# HFPB_01_PAGE-1.net
KiCad netlist of a schematic drawn in Altium Designer
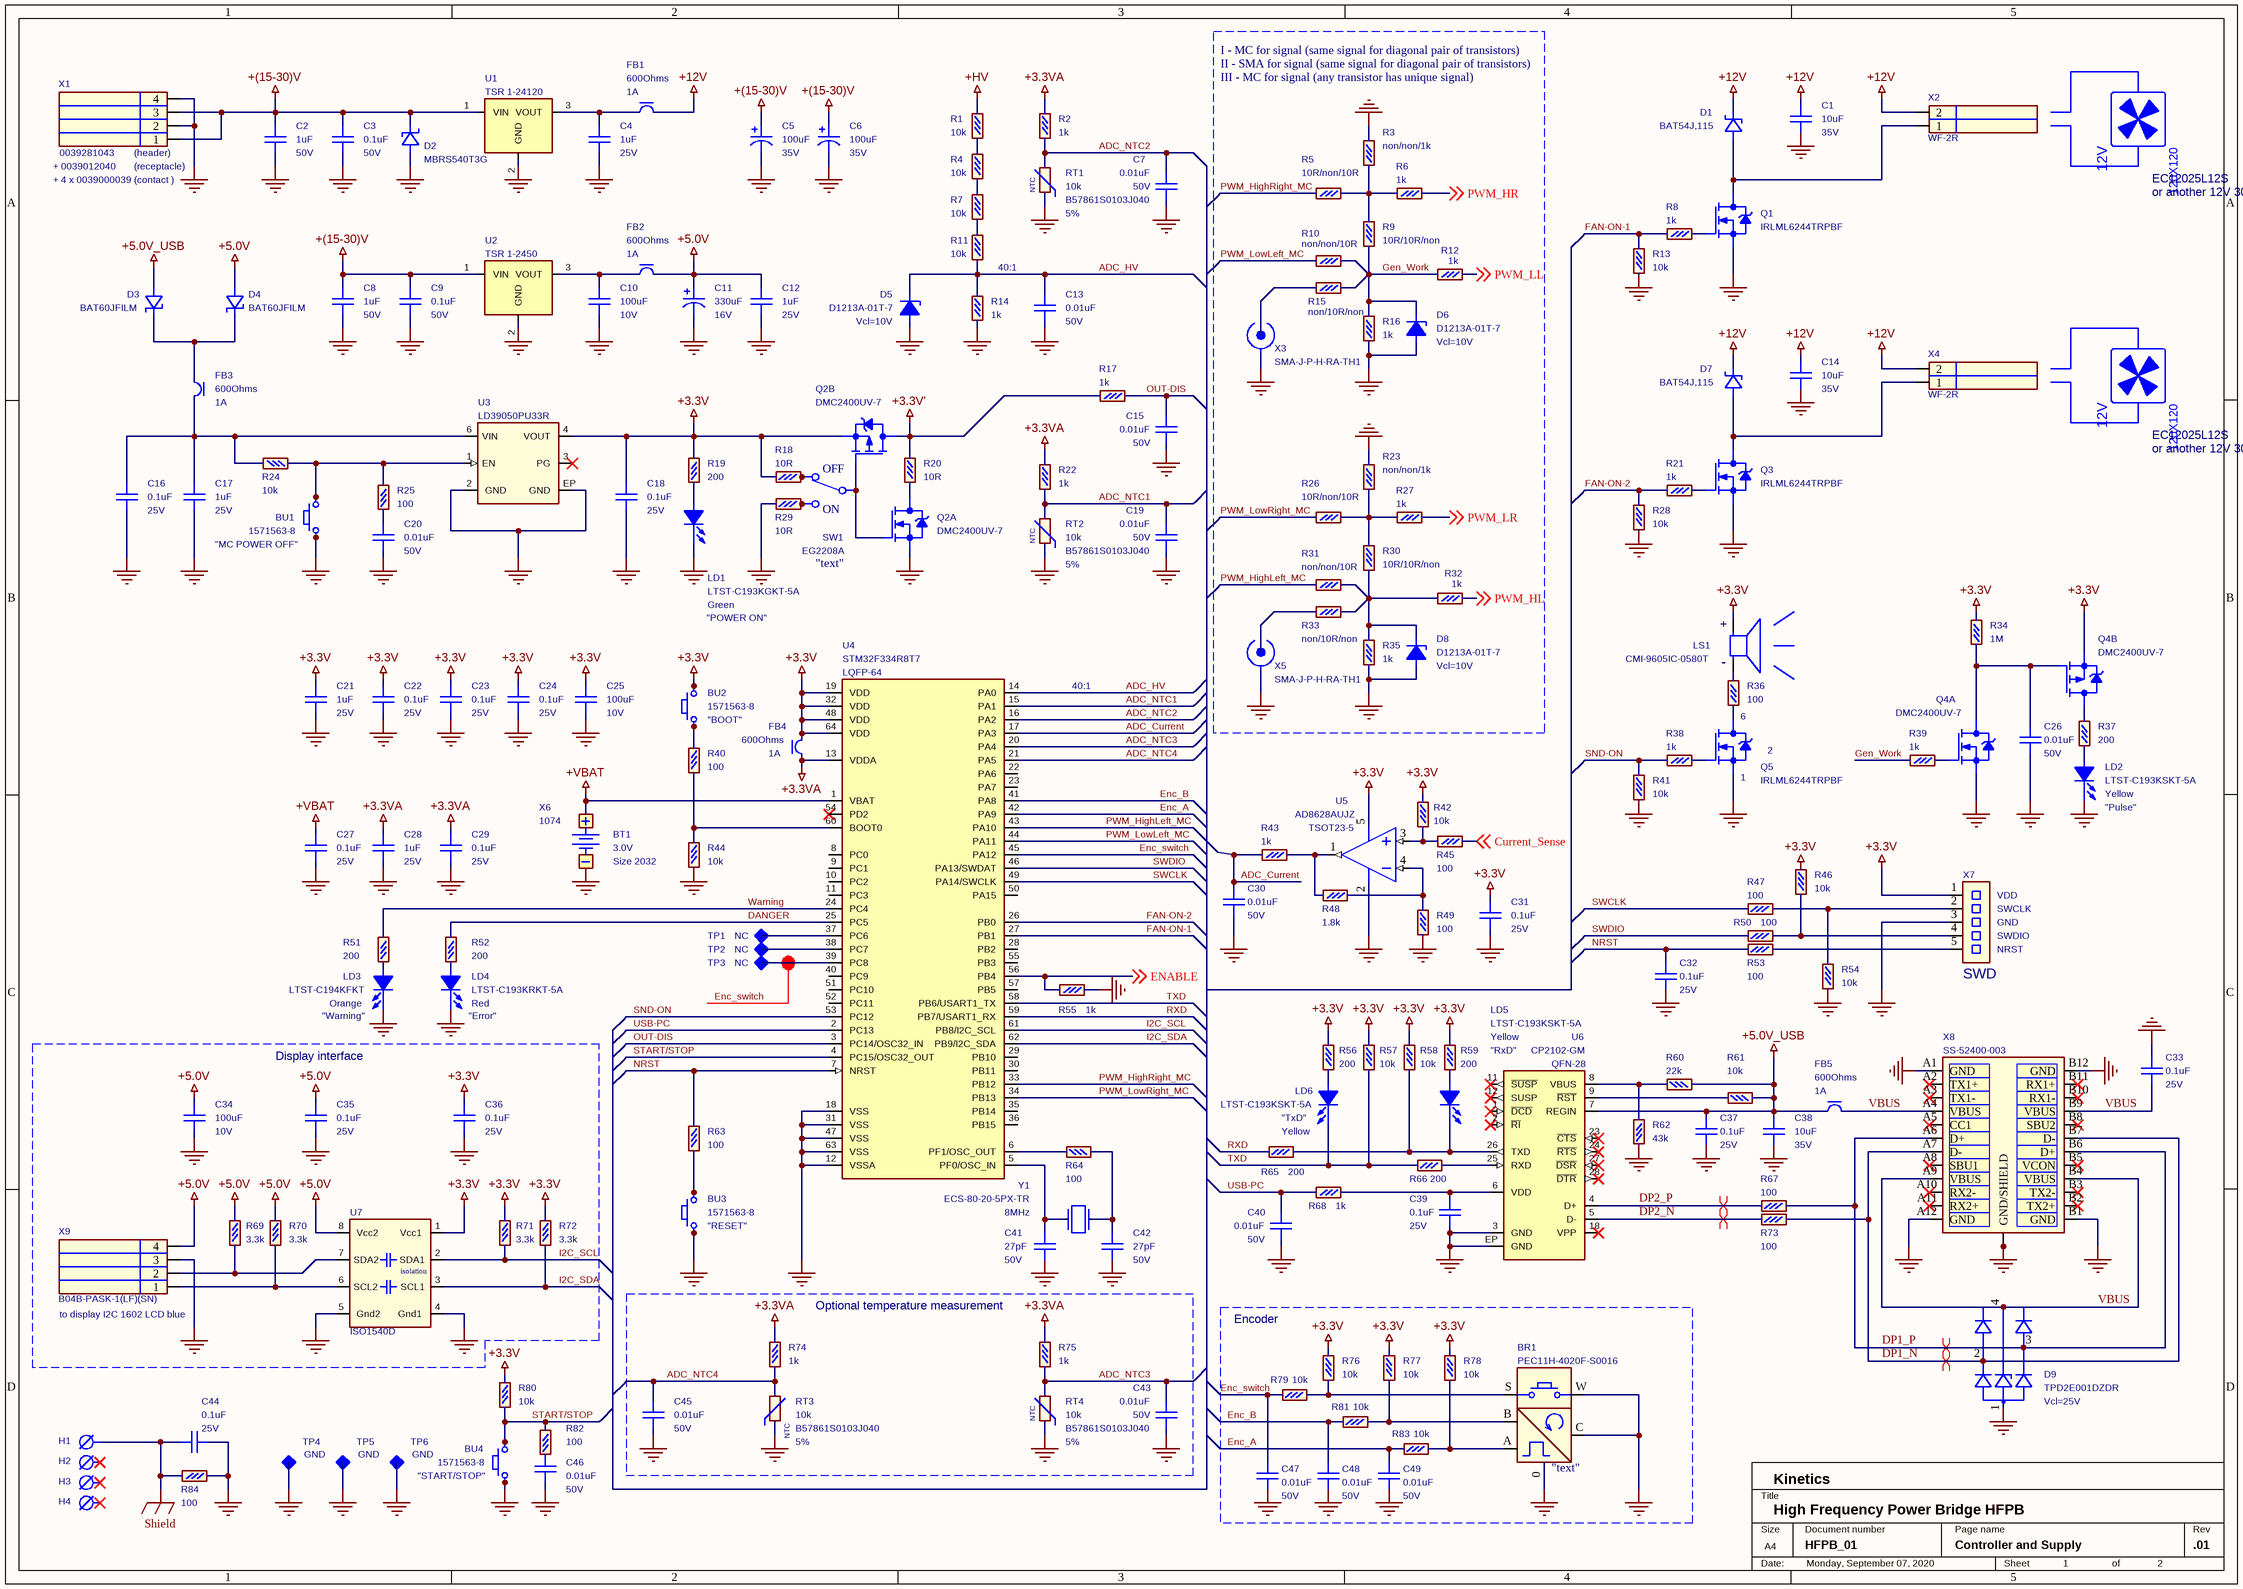
[diagram p0: HFPB_01, PAGE-1.SchDoc]

(export (version "E")
  (design (tool "Eeschema 10.0.6"))
  (components
    (comp (ref "BR1")
      (value "PEC11H-4020F-S0016")
      (footprint "BOURNS_PEC11H")
      (description "Encoder Mechanical 16 PPR")
      (fields (field (name "MANUFACTURER") "BOURNS") (field (name "ALTIUM_VALUE") "\"text\""))
      (libsource (lib "HFPB_01-SchLib") (part "PEC11H-4020F-S0016"))
    )
    (comp (ref "BT1")
      (value "3.0V")
      (description "Battery CR2032")
      (fields (field (name "MANUFACTURER") "* (Panasonic)"))
      (libsource (lib "HFPB_01-SchLib") (part "CR2032"))
    )
    (comp (ref "BU1")
      (value "1571563-8")
      (footprint "TE_1571563-8")
      (description "Switch tactile OFF-(ON) 0.05A 24V")
      (fields
        (field (name "MANUFACTURER") "TE Connectivity")
        (field (name "ALTIUM_VALUE") "\"MC POWER OFF\"")
      )
      (libsource (lib "HFPB_01-SchLib") (part "1571563-8"))
    )
    (comp (ref "BU2")
      (value "1571563-8")
      (footprint "TE_1571563-8")
      (description "Switch tactile OFF-(ON) 0.05A 24V")
      (fields (field (name "MANUFACTURER") "TE Connectivity") (field (name "ALTIUM_VALUE") "\"BOOT\""))
      (libsource (lib "HFPB_01-SchLib") (part "1571563-8"))
    )
    (comp (ref "BU3")
      (value "1571563-8")
      (footprint "TE_1571563-8")
      (description "Switch tactile OFF-(ON) 0.05A 24V")
      (fields (field (name "MANUFACTURER") "TE Connectivity") (field (name "ALTIUM_VALUE") "\"RESET\""))
      (libsource (lib "HFPB_01-SchLib") (part "1571563-8"))
    )
    (comp (ref "BU4")
      (value "1571563-8")
      (footprint "TE_1571563-8")
      (description "Switch tactile OFF-(ON) 0.05A 24V")
      (fields (field (name "MANUFACTURER") "TE Connectivity") (field (name "ALTIUM_VALUE") "\"START/STOP\""))
      (libsource (lib "HFPB_01-SchLib") (part "1571563-8"))
    )
    (comp (ref "C1")
      (value "10uF")
      (footprint "CAPC320X250X280L60N - full legend")
      (description "Capacitor 1210")
      (fields
        (field (name "PART NUMBER") "C1210C106M6PACTU")
        (field (name "MANUFACTURER") "KEMET")
        (field (name "VALUE3") "35V")
      )
      (libsource (lib "HFPB_01-SchLib") (part "C1210"))
    )
    (comp (ref "C2")
      (value "1uF")
      (footprint "CAPC160X80X80L35N - Full legend")
      (description "Capacitor 0603")
      (fields
        (field (name "PART NUMBER") "GRT188R61H105KE13D")
        (field (name "MANUFACTURER") "Murata")
        (field (name "VALUE3") "50V")
      )
      (libsource (lib "HFPB_01-SchLib") (part "C0603"))
    )
    (comp (ref "C3")
      (value "0.1uF")
      (footprint "CAPC160X80X80L35N - Full legend")
      (description "Capacitor 0603")
      (fields
        (field (name "PART NUMBER") "C0603C104K5RAC7082")
        (field (name "MANUFACTURER") "KEMET")
        (field (name "VALUE3") "50V")
      )
      (libsource (lib "HFPB_01-SchLib") (part "C0603"))
    )
    (comp (ref "C4")
      (value "1uF")
      (footprint "CAPC160X80X80L35N - Full legend")
      (description "Capacitor 0603")
      (fields
        (field (name "PART NUMBER") "C1608X7R1E105K080AB")
        (field (name "MANUFACTURER") "TDK")
        (field (name "VALUE3") "25V")
      )
      (libsource (lib "HFPB_01-SchLib") (part "C0603"))
    )
    (comp (ref "C5")
      (value "100uF")
      (footprint "CAPPRD350W60D850H900")
      (description "Capacitor Polymer Radial 100µF 35V 25mOhm")
      (fields
        (field (name "PART NUMBER") "RL81V101MDN1KX")
        (field (name "MANUFACTURER") "Nichicon")
        (field (name "VALUE3") "35V")
      )
      (libsource (lib "HFPB_01-SchLib") (part "RL81V101MDN1KX"))
    )
    (comp (ref "C6")
      (value "100uF")
      (footprint "CAPPRD350W60D850H900")
      (description "Capacitor Polymer Radial 100µF 35V 25mOhm")
      (fields
        (field (name "PART NUMBER") "RL81V101MDN1KX")
        (field (name "MANUFACTURER") "Nichicon")
        (field (name "VALUE3") "35V")
      )
      (libsource (lib "HFPB_01-SchLib") (part "RL81V101MDN1KX"))
    )
    (comp (ref "C7")
      (value "0.01uF")
      (footprint "CAPC160X80X80L35N - Full legend")
      (description "Capacitor 0603")
      (fields
        (field (name "PART NUMBER") "GRM1885C1H103JA01D")
        (field (name "MANUFACTURER") "Murata")
        (field (name "VALUE3") "50V")
      )
      (libsource (lib "HFPB_01-SchLib") (part "C0603"))
    )
    (comp (ref "C8")
      (value "1uF")
      (footprint "CAPC160X80X80L35N - Full legend")
      (description "Capacitor 0603")
      (fields
        (field (name "PART NUMBER") "GRT188R61H105KE13D")
        (field (name "MANUFACTURER") "Murata")
        (field (name "VALUE3") "50V")
      )
      (libsource (lib "HFPB_01-SchLib") (part "C0603"))
    )
    (comp (ref "C9")
      (value "0.1uF")
      (footprint "CAPC160X80X80L35N - Full legend")
      (description "Capacitor 0603")
      (fields
        (field (name "PART NUMBER") "C0603C104K5RAC7082")
        (field (name "MANUFACTURER") "KEMET")
        (field (name "VALUE3") "50V")
      )
      (libsource (lib "HFPB_01-SchLib") (part "C0603"))
    )
    (comp (ref "C10")
      (value "100uF")
      (footprint "CAPC320X250X280L60N - full legend")
      (description "Capacitor 1210")
      (fields
        (field (name "PART NUMBER") "C1210C107M8PACTU")
        (field (name "MANUFACTURER") "KEMET")
        (field (name "VALUE3") "10V")
      )
      (libsource (lib "HFPB_01-SchLib") (part "C1210"))
    )
    (comp (ref "C11")
      (value "330uF")
      (footprint "CAPPRD350W60D850H900")
      (description "Capacitor Polymer Radial 330µF 16V 12mOhm")
      (fields
        (field (name "PART NUMBER") "RL81C331MDN1KX")
        (field (name "MANUFACTURER") "Nichicon")
        (field (name "VALUE3") "16V")
      )
      (libsource (lib "HFPB_01-SchLib") (part "RL81C331MDN1KX"))
    )
    (comp (ref "C12")
      (value "1uF")
      (footprint "CAPC160X80X80L35N - Full legend")
      (description "Capacitor 0603")
      (fields
        (field (name "PART NUMBER") "C1608X7R1E105K080AB")
        (field (name "MANUFACTURER") "TDK")
        (field (name "VALUE3") "25V")
      )
      (libsource (lib "HFPB_01-SchLib") (part "C0603"))
    )
    (comp (ref "C13")
      (value "0.01uF")
      (footprint "CAPC160X80X80L35N - Full legend")
      (description "Capacitor 0603")
      (fields
        (field (name "PART NUMBER") "GRM1885C1H103JA01D")
        (field (name "MANUFACTURER") "Murata")
        (field (name "VALUE3") "50V")
      )
      (libsource (lib "HFPB_01-SchLib") (part "C0603"))
    )
    (comp (ref "C14")
      (value "10uF")
      (footprint "CAPC320X250X280L60N - full legend")
      (description "Capacitor 1210")
      (fields
        (field (name "PART NUMBER") "C1210C106M6PACTU")
        (field (name "MANUFACTURER") "KEMET")
        (field (name "VALUE3") "35V")
      )
      (libsource (lib "HFPB_01-SchLib") (part "C1210"))
    )
    (comp (ref "C15")
      (value "0.01uF")
      (footprint "CAPC160X80X80L35N - Full legend")
      (description "Capacitor 0603")
      (fields
        (field (name "PART NUMBER") "GRM1885C1H103JA01D")
        (field (name "MANUFACTURER") "Murata")
        (field (name "VALUE3") "50V")
      )
      (libsource (lib "HFPB_01-SchLib") (part "C0603"))
    )
    (comp (ref "C16")
      (value "0.1uF")
      (footprint "CAPC160X80X80L35N - Full legend")
      (description "Capacitor 0603")
      (fields
        (field (name "PART NUMBER") "C0603C104K3RAC7082")
        (field (name "MANUFACTURER") "KEMET")
        (field (name "VALUE3") "25V")
      )
      (libsource (lib "HFPB_01-SchLib") (part "C0603"))
    )
    (comp (ref "C17")
      (value "1uF")
      (footprint "CAPC160X80X80L35N - Full legend")
      (description "Capacitor 0603")
      (fields
        (field (name "PART NUMBER") "C1608X7R1E105K080AB")
        (field (name "MANUFACTURER") "TDK")
        (field (name "VALUE3") "25V")
      )
      (libsource (lib "HFPB_01-SchLib") (part "C0603"))
    )
    (comp (ref "C18")
      (value "0.1uF")
      (footprint "CAPC160X80X80L35N - Full legend")
      (description "Capacitor 0603")
      (fields
        (field (name "PART NUMBER") "C0603C104K3RAC7082")
        (field (name "MANUFACTURER") "KEMET")
        (field (name "VALUE3") "25V")
      )
      (libsource (lib "HFPB_01-SchLib") (part "C0603"))
    )
    (comp (ref "C19")
      (value "0.01uF")
      (footprint "CAPC160X80X80L35N - Full legend")
      (description "Capacitor 0603")
      (fields
        (field (name "PART NUMBER") "GRM1885C1H103JA01D")
        (field (name "MANUFACTURER") "Murata")
        (field (name "VALUE3") "50V")
      )
      (libsource (lib "HFPB_01-SchLib") (part "C0603"))
    )
    (comp (ref "C20")
      (value "0.01uF")
      (footprint "CAPC160X80X80L35N - Full legend")
      (description "Capacitor 0603")
      (fields
        (field (name "PART NUMBER") "GRM1885C1H103JA01D")
        (field (name "MANUFACTURER") "Murata")
        (field (name "VALUE3") "50V")
      )
      (libsource (lib "HFPB_01-SchLib") (part "C0603"))
    )
    (comp (ref "C21")
      (value "1uF")
      (footprint "CAPC160X80X80L35N - Full legend")
      (description "Capacitor 0603")
      (fields
        (field (name "PART NUMBER") "C1608X7R1E105K080AB")
        (field (name "MANUFACTURER") "TDK")
        (field (name "VALUE3") "25V")
      )
      (libsource (lib "HFPB_01-SchLib") (part "C0603"))
    )
    (comp (ref "C22")
      (value "0.1uF")
      (footprint "CAPC160X80X80L35N - Full legend")
      (description "Capacitor 0603")
      (fields
        (field (name "PART NUMBER") "C0603C104K3RAC7082")
        (field (name "MANUFACTURER") "KEMET")
        (field (name "VALUE3") "25V")
      )
      (libsource (lib "HFPB_01-SchLib") (part "C0603"))
    )
    (comp (ref "C23")
      (value "0.1uF")
      (footprint "CAPC160X80X80L35N - Full legend")
      (description "Capacitor 0603")
      (fields
        (field (name "PART NUMBER") "C0603C104K3RAC7082")
        (field (name "MANUFACTURER") "KEMET")
        (field (name "VALUE3") "25V")
      )
      (libsource (lib "HFPB_01-SchLib") (part "C0603"))
    )
    (comp (ref "C24")
      (value "0.1uF")
      (footprint "CAPC160X80X80L35N - Full legend")
      (description "Capacitor 0603")
      (fields
        (field (name "PART NUMBER") "C0603C104K3RAC7082")
        (field (name "MANUFACTURER") "KEMET")
        (field (name "VALUE3") "25V")
      )
      (libsource (lib "HFPB_01-SchLib") (part "C0603"))
    )
    (comp (ref "C25")
      (value "100uF")
      (footprint "CAPC320X250X280L60N - full legend")
      (description "Capacitor 1210")
      (fields
        (field (name "PART NUMBER") "C1210C107M8PACTU")
        (field (name "MANUFACTURER") "KEMET")
        (field (name "VALUE3") "10V")
      )
      (libsource (lib "HFPB_01-SchLib") (part "C1210"))
    )
    (comp (ref "C26")
      (value "0.01uF")
      (footprint "CAPC160X80X80L35N - Full legend")
      (description "Capacitor 0603")
      (fields
        (field (name "PART NUMBER") "GRM1885C1H103JA01D")
        (field (name "MANUFACTURER") "Murata")
        (field (name "VALUE3") "50V")
      )
      (libsource (lib "HFPB_01-SchLib") (part "C0603"))
    )
    (comp (ref "C27")
      (value "0.1uF")
      (footprint "CAPC160X80X80L35N - Full legend")
      (description "Capacitor 0603")
      (fields
        (field (name "PART NUMBER") "C0603C104K3RAC7082")
        (field (name "MANUFACTURER") "KEMET")
        (field (name "VALUE3") "25V")
      )
      (libsource (lib "HFPB_01-SchLib") (part "C0603"))
    )
    (comp (ref "C28")
      (value "1uF")
      (footprint "CAPC160X80X80L35N - Full legend")
      (description "Capacitor 0603")
      (fields
        (field (name "PART NUMBER") "C1608X7R1E105K080AB")
        (field (name "MANUFACTURER") "TDK")
        (field (name "VALUE3") "25V")
      )
      (libsource (lib "HFPB_01-SchLib") (part "C0603"))
    )
    (comp (ref "C29")
      (value "0.1uF")
      (footprint "CAPC160X80X80L35N - Full legend")
      (description "Capacitor 0603")
      (fields
        (field (name "PART NUMBER") "C0603C104K3RAC7082")
        (field (name "MANUFACTURER") "KEMET")
        (field (name "VALUE3") "25V")
      )
      (libsource (lib "HFPB_01-SchLib") (part "C0603"))
    )
    (comp (ref "C30")
      (value "0.01uF")
      (footprint "CAPC160X80X80L35N - Full legend")
      (description "Capacitor 0603")
      (fields
        (field (name "PART NUMBER") "GRM1885C1H103JA01D")
        (field (name "MANUFACTURER") "Murata")
        (field (name "VALUE3") "50V")
      )
      (libsource (lib "HFPB_01-SchLib") (part "C0603"))
    )
    (comp (ref "C31")
      (value "0.1uF")
      (footprint "CAPC160X80X80L35N - Full legend")
      (description "Capacitor 0603")
      (fields
        (field (name "PART NUMBER") "C0603C104K3RAC7082")
        (field (name "MANUFACTURER") "KEMET")
        (field (name "VALUE3") "25V")
      )
      (libsource (lib "HFPB_01-SchLib") (part "C0603"))
    )
    (comp (ref "C32")
      (value "0.1uF")
      (footprint "CAPC160X80X80L35N - Full legend")
      (description "Capacitor 0603")
      (fields
        (field (name "PART NUMBER") "C0603C104K3RAC7082")
        (field (name "MANUFACTURER") "KEMET")
        (field (name "VALUE3") "25V")
      )
      (libsource (lib "HFPB_01-SchLib") (part "C0603"))
    )
    (comp (ref "C33")
      (value "0.1uF")
      (footprint "CAPC160X80X80L35N - Full legend")
      (description "Capacitor 0603")
      (fields
        (field (name "PART NUMBER") "C0603C104K3RAC7082")
        (field (name "MANUFACTURER") "KEMET")
        (field (name "VALUE3") "25V")
      )
      (libsource (lib "HFPB_01-SchLib") (part "C0603"))
    )
    (comp (ref "C34")
      (value "100uF")
      (footprint "CAPC320X250X280L60N - full legend")
      (description "Capacitor 1210")
      (fields
        (field (name "PART NUMBER") "C1210C107M8PACTU")
        (field (name "MANUFACTURER") "KEMET")
        (field (name "VALUE3") "10V")
      )
      (libsource (lib "HFPB_01-SchLib") (part "C1210"))
    )
    (comp (ref "C35")
      (value "0.1uF")
      (footprint "CAPC160X80X80L35N - Full legend")
      (description "Capacitor 0603")
      (fields
        (field (name "PART NUMBER") "C0603C104K3RAC7082")
        (field (name "MANUFACTURER") "KEMET")
        (field (name "VALUE3") "25V")
      )
      (libsource (lib "HFPB_01-SchLib") (part "C0603"))
    )
    (comp (ref "C36")
      (value "0.1uF")
      (footprint "CAPC160X80X80L35N - Full legend")
      (description "Capacitor 0603")
      (fields
        (field (name "PART NUMBER") "C0603C104K3RAC7082")
        (field (name "MANUFACTURER") "KEMET")
        (field (name "VALUE3") "25V")
      )
      (libsource (lib "HFPB_01-SchLib") (part "C0603"))
    )
    (comp (ref "C37")
      (value "0.1uF")
      (footprint "CAPC160X80X80L35N - Full legend")
      (description "Capacitor 0603")
      (fields
        (field (name "PART NUMBER") "C0603C104K3RAC7082")
        (field (name "MANUFACTURER") "KEMET")
        (field (name "VALUE3") "25V")
      )
      (libsource (lib "HFPB_01-SchLib") (part "C0603"))
    )
    (comp (ref "C38")
      (value "10uF")
      (footprint "CAPC320X250X280L60N - full legend")
      (description "Capacitor 1210")
      (fields
        (field (name "PART NUMBER") "C1210C106M6PACTU")
        (field (name "MANUFACTURER") "KEMET")
        (field (name "VALUE3") "35V")
      )
      (libsource (lib "HFPB_01-SchLib") (part "C1210"))
    )
    (comp (ref "C39")
      (value "0.1uF")
      (footprint "CAPC160X80X80L35N - Full legend")
      (description "Capacitor 0603")
      (fields
        (field (name "PART NUMBER") "C0603C104K3RAC7082")
        (field (name "MANUFACTURER") "KEMET")
        (field (name "VALUE3") "25V")
      )
      (libsource (lib "HFPB_01-SchLib") (part "C0603"))
    )
    (comp (ref "C40")
      (value "0.01uF")
      (footprint "CAPC160X80X80L35N - Full legend")
      (description "Capacitor 0603")
      (fields
        (field (name "PART NUMBER") "GRM1885C1H103JA01D")
        (field (name "MANUFACTURER") "Murata")
        (field (name "VALUE3") "50V")
      )
      (libsource (lib "HFPB_01-SchLib") (part "C0603"))
    )
    (comp (ref "C41")
      (value "27pF")
      (footprint "CAPC160X80X80L35N - Full legend")
      (description "Capacitor 0603")
      (fields
        (field (name "PART NUMBER") "C0603C270J5GAC7411")
        (field (name "MANUFACTURER") "KEMET")
        (field (name "VALUE3") "50V")
      )
      (libsource (lib "HFPB_01-SchLib") (part "C0603"))
    )
    (comp (ref "C42")
      (value "27pF")
      (footprint "CAPC160X80X80L35N - Full legend")
      (description "Capacitor 0603")
      (fields
        (field (name "PART NUMBER") "C0603C270J5GAC7411")
        (field (name "MANUFACTURER") "KEMET")
        (field (name "VALUE3") "50V")
      )
      (libsource (lib "HFPB_01-SchLib") (part "C0603"))
    )
    (comp (ref "C43")
      (value "0.01uF")
      (footprint "CAPC160X80X80L35N - Full legend")
      (description "Capacitor 0603")
      (fields
        (field (name "PART NUMBER") "GRM1885C1H103JA01D")
        (field (name "MANUFACTURER") "Murata")
        (field (name "VALUE3") "50V")
      )
      (libsource (lib "HFPB_01-SchLib") (part "C0603"))
    )
    (comp (ref "C44")
      (value "0.1uF")
      (footprint "CAPC160X80X80L35N - Full legend")
      (description "Capacitor 0603")
      (fields
        (field (name "PART NUMBER") "C0603C104K3RAC7082")
        (field (name "MANUFACTURER") "KEMET")
        (field (name "VALUE3") "25V")
      )
      (libsource (lib "HFPB_01-SchLib") (part "C0603"))
    )
    (comp (ref "C45")
      (value "0.01uF")
      (footprint "CAPC160X80X80L35N - Full legend")
      (description "Capacitor 0603")
      (fields
        (field (name "PART NUMBER") "GRM1885C1H103JA01D")
        (field (name "MANUFACTURER") "Murata")
        (field (name "VALUE3") "50V")
      )
      (libsource (lib "HFPB_01-SchLib") (part "C0603"))
    )
    (comp (ref "C46")
      (value "0.01uF")
      (footprint "CAPC160X80X80L35N - Full legend")
      (description "Capacitor 0603")
      (fields
        (field (name "PART NUMBER") "GRM1885C1H103JA01D")
        (field (name "MANUFACTURER") "Murata")
        (field (name "VALUE3") "50V")
      )
      (libsource (lib "HFPB_01-SchLib") (part "C0603"))
    )
    (comp (ref "C47")
      (value "0.01uF")
      (footprint "CAPC160X80X80L35N - Full legend")
      (description "Capacitor 0603")
      (fields
        (field (name "PART NUMBER") "GRM1885C1H103JA01D")
        (field (name "MANUFACTURER") "Murata")
        (field (name "VALUE3") "50V")
      )
      (libsource (lib "HFPB_01-SchLib") (part "C0603"))
    )
    (comp (ref "C48")
      (value "0.01uF")
      (footprint "CAPC160X80X80L35N - Full legend")
      (description "Capacitor 0603")
      (fields
        (field (name "PART NUMBER") "GRM1885C1H103JA01D")
        (field (name "MANUFACTURER") "Murata")
        (field (name "VALUE3") "50V")
      )
      (libsource (lib "HFPB_01-SchLib") (part "C0603"))
    )
    (comp (ref "C49")
      (value "0.01uF")
      (footprint "CAPC160X80X80L35N - Full legend")
      (description "Capacitor 0603")
      (fields
        (field (name "PART NUMBER") "GRM1885C1H103JA01D")
        (field (name "MANUFACTURER") "Murata")
        (field (name "VALUE3") "50V")
      )
      (libsource (lib "HFPB_01-SchLib") (part "C0603"))
    )
    (comp (ref "D1")
      (value "BAT54J,115")
      (footprint "SODFL250X125X80L40X32N")
      (description "Diode Schottky 30V 0.2A")
      (fields (field (name "MANUFACTURER") "Nexperia"))
      (libsource (lib "HFPB_01-SchLib") (part "BAT54J,115"))
    )
    (comp (ref "D2")
      (value "MBRS540T3G")
      (footprint "DIOM795X585X240L100X300N")
      (description "Diode Schottky 40V 5A")
      (fields (field (name "MANUFACTURER") "ON Semiconductor"))
      (libsource (lib "HFPB_01-SchLib") (part "MBRS540T3G"))
    )
    (comp (ref "D3")
      (value "BAT60JFILM")
      (footprint "SOD250X125X110L30X32N")
      (description "Diode Schottky 10V 3A")
      (fields (field (name "MANUFACTURER") "STM"))
      (libsource (lib "HFPB_01-SchLib") (part "BAT60JFILM"))
    )
    (comp (ref "D4")
      (value "BAT60JFILM")
      (footprint "SOD250X125X110L30X32N")
      (description "Diode Schottky 10V 3A")
      (fields (field (name "MANUFACTURER") "STM"))
      (libsource (lib "HFPB_01-SchLib") (part "BAT60JFILM"))
    )
    (comp (ref "D5")
      (value "D1213A-01T-7")
      (footprint "SODFL160X80X65L30X30N")
      (description "TVS Diode Vstand=3.3V Vclamp=10V")
      (fields (field (name "MANUFACTURER") "Diodes Inc.") (field (name "VALUE2") "Vcl=10V"))
      (libsource (lib "HFPB_01-SchLib") (part "D1213A-01T-7"))
    )
    (comp (ref "D6")
      (value "D1213A-01T-7")
      (footprint "SODFL160X80X65L30X30N")
      (description "TVS Diode Vstand=3.3V Vclamp=10V")
      (fields (field (name "MANUFACTURER") "Diodes Inc.") (field (name "VALUE2") "Vcl=10V"))
      (libsource (lib "HFPB_01-SchLib") (part "D1213A-01T-7"))
    )
    (comp (ref "D7")
      (value "BAT54J,115")
      (footprint "SODFL250X125X80L40X32N")
      (description "Diode Schottky 30V 0.2A")
      (fields (field (name "MANUFACTURER") "Nexperia"))
      (libsource (lib "HFPB_01-SchLib") (part "BAT54J,115"))
    )
    (comp (ref "D8")
      (value "D1213A-01T-7")
      (footprint "SODFL160X80X65L30X30N")
      (description "TVS Diode Vstand=3.3V Vclamp=10V")
      (fields (field (name "MANUFACTURER") "Diodes Inc.") (field (name "VALUE2") "Vcl=10V"))
      (libsource (lib "HFPB_01-SchLib") (part "D1213A-01T-7"))
    )
    (comp (ref "D9")
      (value "TPD2E001DZDR")
      (footprint "SOT143-4P192_237X122L40X40N")
      (description "TVS Diode Vstand=5.5V Vbr=11V")
      (fields (field (name "MANUFACTURER") "Texas Instruments") (field (name "VALUE2") "Vcl=25V"))
      (libsource (lib "HFPB_01-SchLib") (part "TPD2E001DZDR"))
    )
    (comp (ref "FB1")
      (value "600Ohms")
      (footprint "BEADC160X80X80L30N")
      (description "Ferrite Bead 600Ohms 1A")
      (fields
        (field (name "PART NUMBER") "MPZ1608S601ATA00")
        (field (name "MANUFACTURER") "TDK")
        (field (name "VALUE1") "1A")
      )
      (libsource (lib "HFPB_01-SchLib") (part "MPZ1608S601ATA00"))
    )
    (comp (ref "FB2")
      (value "600Ohms")
      (footprint "BEADC160X80X80L30N")
      (description "Ferrite Bead 600Ohms 1A")
      (fields
        (field (name "PART NUMBER") "MPZ1608S601ATA00")
        (field (name "MANUFACTURER") "TDK")
        (field (name "VALUE1") "1A")
      )
      (libsource (lib "HFPB_01-SchLib") (part "MPZ1608S601ATA00"))
    )
    (comp (ref "FB3")
      (value "600Ohms")
      (footprint "BEADC160X80X80L30N")
      (description "Ferrite Bead 600Ohms 1A")
      (fields
        (field (name "PART NUMBER") "MPZ1608S601ATA00")
        (field (name "MANUFACTURER") "TDK")
        (field (name "VALUE1") "1A")
      )
      (libsource (lib "HFPB_01-SchLib") (part "MPZ1608S601ATA00"))
    )
    (comp (ref "FB4")
      (value "600Ohms")
      (footprint "BEADC160X80X80L30N")
      (description "Ferrite Bead 600Ohms 1A")
      (fields
        (field (name "PART NUMBER") "MPZ1608S601ATA00")
        (field (name "MANUFACTURER") "TDK")
        (field (name "VALUE1") "1A")
      )
      (libsource (lib "HFPB_01-SchLib") (part "MPZ1608S601ATA00"))
    )
    (comp (ref "FB5")
      (value "600Ohms")
      (footprint "BEADC160X80X80L30N")
      (description "Ferrite Bead 600Ohms 1A")
      (fields
        (field (name "PART NUMBER") "MPZ1608S601ATA00")
        (field (name "MANUFACTURER") "TDK")
        (field (name "VALUE1") "1A")
      )
      (libsource (lib "HFPB_01-SchLib") (part "MPZ1608S601ATA00"))
    )
    (comp (ref "H1")
      (value "~")
      (footprint "hole/3.5/4.5-O")
      (description "HOLE 3.5mm")
      (libsource (lib "HFPB_01-SchLib") (part "HOLE/3.5"))
    )
    (comp (ref "H2")
      (value "~")
      (footprint "hole/3.5/4.5-O")
      (description "HOLE 3.5mm")
      (libsource (lib "HFPB_01-SchLib") (part "HOLE/3.5"))
    )
    (comp (ref "H3")
      (value "~")
      (footprint "hole/3.5/4.5-O")
      (description "HOLE 3.5mm")
      (libsource (lib "HFPB_01-SchLib") (part "HOLE/3.5"))
    )
    (comp (ref "H4")
      (value "~")
      (footprint "hole/3.5/4.5-O")
      (description "HOLE 3.5mm")
      (libsource (lib "HFPB_01-SchLib") (part "HOLE/3.5"))
    )
    (comp (ref "LD1")
      (value "LTST-C193KGKT-5A")
      (footprint "LEDC160X80X40L30N")
      (description "LED 0603")
      (fields
        (field (name "MANUFACTURER") "Lite-On Inc.")
        (field (name "ALTIUM_VALUE") "Green")
        (field (name "TEXT") "\"POWER ON\"")
      )
      (libsource (lib "HFPB_01-SchLib") (part "LED0603"))
    )
    (comp (ref "LD2")
      (value "LTST-C193KSKT-5A")
      (footprint "LEDC160X80X40L30N")
      (description "LED 0603")
      (fields
        (field (name "MANUFACTURER") "Lite-On Inc.")
        (field (name "TEXT") "\"Pulse\"")
        (field (name "ALTIUM_VALUE") "Yellow")
      )
      (libsource (lib "HFPB_01-SchLib") (part "LED0603"))
    )
    (comp (ref "LD3")
      (value "LTST-C194KFKT")
      (footprint "LEDC160X80X40L30N")
      (description "LED 0603")
      (fields
        (field (name "MANUFACTURER") "Lite-On Inc.")
        (field (name "ALTIUM_VALUE") "Orange")
        (field (name "TEXT") "\"Warning\"")
      )
      (libsource (lib "HFPB_01-SchLib") (part "LED0603"))
    )
    (comp (ref "LD4")
      (value "LTST-C193KRKT-5A")
      (footprint "LEDC160X80X40L30N")
      (description "LED 0603")
      (fields
        (field (name "MANUFACTURER") "Lite-On Inc.")
        (field (name "ALTIUM_VALUE") "Red")
        (field (name "TEXT") "\"Error\"")
      )
      (libsource (lib "HFPB_01-SchLib") (part "LED0603"))
    )
    (comp (ref "LD5")
      (value "LTST-C193KSKT-5A")
      (footprint "LEDC160X80X40L30N")
      (description "LED 0603")
      (fields
        (field (name "MANUFACTURER") "Lite-On Inc.")
        (field (name "TEXT") "\"RxD\"")
        (field (name "ALTIUM_VALUE") "Yellow")
      )
      (libsource (lib "HFPB_01-SchLib") (part "LED0603"))
    )
    (comp (ref "LD6")
      (value "LTST-C193KSKT-5A")
      (footprint "LEDC160X80X40L30N")
      (description "LED 0603")
      (fields
        (field (name "MANUFACTURER") "Lite-On Inc.")
        (field (name "TEXT") "\"TxD\"")
        (field (name "ALTIUM_VALUE") "Yellow")
      )
      (libsource (lib "HFPB_01-SchLib") (part "LED0603"))
    )
    (comp (ref "LS1")
      (value "CMI-9605IC-0580T")
      (footprint "CUI_CMI-9605IC-0580T")
      (description "Buzzer Magnetic Audio Indicator 5V 80dB 2.7kHz")
      (fields (field (name "MANUFACTURER") "CUI"))
      (libsource (lib "HFPB_01-SchLib") (part "CMI-9605IC-0580T"))
    )
    (comp (ref "Q1")
      (value "IRLML6244TRPBF")
      (footprint "SOT23-3P95_235X110L50X40N")
      (description "MOSFET N-channel, 20V, 21mOhm")
      (fields (field (name "MANUFACTURER") "Infineon"))
      (libsource (lib "HFPB_01-SchLib") (part "IRLML6244TRPBF"))
    )
    (comp (ref "Q2")
      (value "DMC2400UV-7")
      (footprint "TRXSOFL6P50_160X162X60L20X22N")
      (description "Transistors N-channel, P-channel (Dual) MOSFET, 20V, 1A")
      (fields (field (name "MANUFACTURER") "Diodes Inc."))
      (libsource (lib "HFPB_01-SchLib") (part "DMC2400UV-7"))
    )
    (comp (ref "Q3")
      (value "IRLML6244TRPBF")
      (footprint "SOT23-3P95_235X110L50X40N")
      (description "MOSFET N-channel, 20V, 21mOhm")
      (fields (field (name "MANUFACTURER") "Infineon"))
      (libsource (lib "HFPB_01-SchLib") (part "IRLML6244TRPBF"))
    )
    (comp (ref "Q4")
      (value "DMC2400UV-7")
      (footprint "TRXSOFL6P50_160X162X60L20X22N")
      (description "Transistors N-channel, P-channel (Dual) MOSFET, 20V, 1A")
      (fields (field (name "MANUFACTURER") "Diodes Inc."))
      (libsource (lib "HFPB_01-SchLib") (part "DMC2400UV-7"))
    )
    (comp (ref "Q5")
      (value "IRLML6244TRPBF")
      (footprint "SOT23-3P95_235X110L50X40N")
      (description "MOSFET N-channel, 20V, 21mOhm")
      (fields (field (name "MANUFACTURER") "Infineon"))
      (libsource (lib "HFPB_01-SchLib") (part "IRLML6244TRPBF"))
    )
    (comp (ref "R1")
      (value "10k")
      (footprint "RESC160X80X55L30N - Full legend")
      (description "Resistor 0603")
      (fields (field (name "PART NUMBER") "ERJ-3EKF1002V") (field (name "MANUFACTURER") "Panasonic"))
      (libsource (lib "HFPB_01-SchLib") (part "R0603"))
    )
    (comp (ref "R2")
      (value "1k")
      (footprint "RESC160X80X55L30N - Full legend")
      (description "Resistor 0603")
      (fields (field (name "PART NUMBER") "ERJ-3EKF1001V") (field (name "MANUFACTURER") "Panasonic"))
      (libsource (lib "HFPB_01-SchLib") (part "R0603"))
    )
    (comp (ref "R3")
      (value "non/non/1k")
      (footprint "RESC160X80X55L30N - Full legend")
      (description "Resistor 0603")
      (fields (field (name "PART NUMBER") "ERJ-3EKF1001V") (field (name "MANUFACTURER") "Panasonic"))
      (libsource (lib "") (part "R0603_3"))
    )
    (comp (ref "R4")
      (value "10k")
      (footprint "RESC160X80X55L30N - Full legend")
      (description "Resistor 0603")
      (fields (field (name "PART NUMBER") "ERJ-3EKF1002V") (field (name "MANUFACTURER") "Panasonic"))
      (libsource (lib "HFPB_01-SchLib") (part "R0603"))
    )
    (comp (ref "R5")
      (value "10R/non/10R")
      (footprint "RESC160X80X55L30N - Full legend")
      (description "Resistor 0603")
      (fields (field (name "PART NUMBER") "ERJ-3EKF10R0V") (field (name "MANUFACTURER") "Panasonic"))
      (libsource (lib "") (part "R0603_1"))
    )
    (comp (ref "R6")
      (value "1k")
      (footprint "RESC160X80X55L30N - Full legend")
      (description "Resistor 0603")
      (fields (field (name "PART NUMBER") "ERJ-3EKF1001V") (field (name "MANUFACTURER") "Panasonic"))
      (libsource (lib "") (part "R0603_1"))
    )
    (comp (ref "R7")
      (value "10k")
      (footprint "RESC160X80X55L30N - Full legend")
      (description "Resistor 0603")
      (fields (field (name "PART NUMBER") "ERJ-3EKF1002V") (field (name "MANUFACTURER") "Panasonic"))
      (libsource (lib "HFPB_01-SchLib") (part "R0603"))
    )
    (comp (ref "R8")
      (value "1k")
      (footprint "RESC160X80X55L30N - Full legend")
      (description "Resistor 0603")
      (fields (field (name "PART NUMBER") "ERJ-3EKF1001V") (field (name "MANUFACTURER") "Panasonic"))
      (libsource (lib "") (part "R0603_1"))
    )
    (comp (ref "R9")
      (value "10R/10R/non")
      (footprint "RESC160X80X55L30N - Full legend")
      (description "Resistor 0603")
      (fields (field (name "PART NUMBER") "ERJ-3EKF10R0V") (field (name "MANUFACTURER") "Panasonic"))
      (libsource (lib "HFPB_01-SchLib") (part "R0603"))
    )
    (comp (ref "R10")
      (value "non/non/10R")
      (footprint "RESC160X80X55L30N - Full legend")
      (description "Resistor 0603")
      (fields (field (name "PART NUMBER") "ERJ-3EKF10R0V") (field (name "MANUFACTURER") "Panasonic"))
      (libsource (lib "") (part "R0603_1"))
    )
    (comp (ref "R11")
      (value "10k")
      (footprint "RESC160X80X55L30N - Full legend")
      (description "Resistor 0603")
      (fields (field (name "PART NUMBER") "ERJ-3EKF1002V") (field (name "MANUFACTURER") "Panasonic"))
      (libsource (lib "HFPB_01-SchLib") (part "R0603"))
    )
    (comp (ref "R12")
      (value "1k")
      (footprint "RESC160X80X55L30N - Full legend")
      (description "Resistor 0603")
      (fields (field (name "PART NUMBER") "ERJ-3EKF1001V") (field (name "MANUFACTURER") "Panasonic"))
      (libsource (lib "") (part "R0603_1"))
    )
    (comp (ref "R13")
      (value "10k")
      (footprint "RESC160X80X55L30N - Full legend")
      (description "Resistor 0603")
      (fields (field (name "PART NUMBER") "ERJ-3EKF1002V") (field (name "MANUFACTURER") "Panasonic"))
      (libsource (lib "HFPB_01-SchLib") (part "R0603"))
    )
    (comp (ref "R14")
      (value "1k")
      (footprint "RESC160X80X55L30N - Full legend")
      (description "Resistor 0603")
      (fields (field (name "PART NUMBER") "ERJ-3EKF1001V") (field (name "MANUFACTURER") "Panasonic"))
      (libsource (lib "HFPB_01-SchLib") (part "R0603"))
    )
    (comp (ref "R15")
      (value "non/10R/non")
      (footprint "RESC160X80X55L30N - Full legend")
      (description "Resistor 0603")
      (fields (field (name "PART NUMBER") "ERJ-3EKF10R0V") (field (name "MANUFACTURER") "Panasonic"))
      (libsource (lib "") (part "R0603_1"))
    )
    (comp (ref "R16")
      (value "1k")
      (footprint "RESC160X80X55L30N - Full legend")
      (description "Resistor 0603")
      (fields (field (name "PART NUMBER") "ERJ-3EKF1001V") (field (name "MANUFACTURER") "Panasonic"))
      (libsource (lib "") (part "R0603_3"))
    )
    (comp (ref "R17")
      (value "1k")
      (footprint "RESC160X80X55L30N - Full legend")
      (description "Resistor 0603")
      (fields (field (name "PART NUMBER") "ERJ-3EKF1001V") (field (name "MANUFACTURER") "Panasonic"))
      (libsource (lib "") (part "R0603_1"))
    )
    (comp (ref "R18")
      (value "10R")
      (footprint "RESC160X80X55L30N - Full legend")
      (description "Resistor 0603")
      (fields (field (name "PART NUMBER") "ERJ-3EKF10R0V") (field (name "MANUFACTURER") "Panasonic"))
      (libsource (lib "") (part "R0603_2"))
    )
    (comp (ref "R19")
      (value "200")
      (footprint "RESC160X80X55L30N - Full legend")
      (description "Resistor 0603")
      (fields (field (name "PART NUMBER") "ERJ-3EKF2000V") (field (name "MANUFACTURER") "Panasonic"))
      (libsource (lib "") (part "R0603_2"))
    )
    (comp (ref "R20")
      (value "10R")
      (footprint "RESC160X80X55L30N - Full legend")
      (description "Resistor 0603")
      (fields (field (name "PART NUMBER") "ERJ-3EKF10R0V") (field (name "MANUFACTURER") "Panasonic"))
      (libsource (lib "HFPB_01-SchLib") (part "R0603"))
    )
    (comp (ref "R21")
      (value "1k")
      (footprint "RESC160X80X55L30N - Full legend")
      (description "Resistor 0603")
      (fields (field (name "PART NUMBER") "ERJ-3EKF1001V") (field (name "MANUFACTURER") "Panasonic"))
      (libsource (lib "") (part "R0603_1"))
    )
    (comp (ref "R22")
      (value "1k")
      (footprint "RESC160X80X55L30N - Full legend")
      (description "Resistor 0603")
      (fields (field (name "PART NUMBER") "ERJ-3EKF1001V") (field (name "MANUFACTURER") "Panasonic"))
      (libsource (lib "HFPB_01-SchLib") (part "R0603"))
    )
    (comp (ref "R23")
      (value "non/non/1k")
      (footprint "RESC160X80X55L30N - Full legend")
      (description "Resistor 0603")
      (fields (field (name "PART NUMBER") "ERJ-3EKF1001V") (field (name "MANUFACTURER") "Panasonic"))
      (libsource (lib "") (part "R0603_3"))
    )
    (comp (ref "R24")
      (value "10k")
      (footprint "RESC160X80X55L30N - Full legend")
      (description "Resistor 0603")
      (fields (field (name "PART NUMBER") "ERJ-3EKF1002V") (field (name "MANUFACTURER") "Panasonic"))
      (libsource (lib "HFPB_01-SchLib") (part "R0603"))
    )
    (comp (ref "R25")
      (value "100")
      (footprint "RESC160X80X55L30N - Full legend")
      (description "Resistor 0603")
      (fields (field (name "PART NUMBER") "ERJ-3EKF1000V") (field (name "MANUFACTURER") "Panasonic"))
      (libsource (lib "") (part "R0603_2"))
    )
    (comp (ref "R26")
      (value "10R/non/10R")
      (footprint "RESC160X80X55L30N - Full legend")
      (description "Resistor 0603")
      (fields (field (name "PART NUMBER") "ERJ-3EKF10R0V") (field (name "MANUFACTURER") "Panasonic"))
      (libsource (lib "") (part "R0603_1"))
    )
    (comp (ref "R27")
      (value "1k")
      (footprint "RESC160X80X55L30N - Full legend")
      (description "Resistor 0603")
      (fields (field (name "PART NUMBER") "ERJ-3EKF1001V") (field (name "MANUFACTURER") "Panasonic"))
      (libsource (lib "") (part "R0603_1"))
    )
    (comp (ref "R28")
      (value "10k")
      (footprint "RESC160X80X55L30N - Full legend")
      (description "Resistor 0603")
      (fields (field (name "PART NUMBER") "ERJ-3EKF1002V") (field (name "MANUFACTURER") "Panasonic"))
      (libsource (lib "HFPB_01-SchLib") (part "R0603"))
    )
    (comp (ref "R29")
      (value "10R")
      (footprint "RESC160X80X55L30N - Full legend")
      (description "Resistor 0603")
      (fields (field (name "PART NUMBER") "ERJ-3EKF10R0V") (field (name "MANUFACTURER") "Panasonic"))
      (libsource (lib "") (part "R0603_2"))
    )
    (comp (ref "R30")
      (value "10R/10R/non")
      (footprint "RESC160X80X55L30N - Full legend")
      (description "Resistor 0603")
      (fields (field (name "PART NUMBER") "ERJ-3EKF10R0V") (field (name "MANUFACTURER") "Panasonic"))
      (libsource (lib "HFPB_01-SchLib") (part "R0603"))
    )
    (comp (ref "R31")
      (value "non/non/10R")
      (footprint "RESC160X80X55L30N - Full legend")
      (description "Resistor 0603")
      (fields (field (name "PART NUMBER") "ERJ-3EKF10R0V") (field (name "MANUFACTURER") "Panasonic"))
      (libsource (lib "") (part "R0603_1"))
    )
    (comp (ref "R32")
      (value "1k")
      (footprint "RESC160X80X55L30N - Full legend")
      (description "Resistor 0603")
      (fields (field (name "PART NUMBER") "ERJ-3EKF1001V") (field (name "MANUFACTURER") "Panasonic"))
      (libsource (lib "") (part "R0603_1"))
    )
    (comp (ref "R33")
      (value "non/10R/non")
      (footprint "RESC160X80X55L30N - Full legend")
      (description "Resistor 0603")
      (fields (field (name "PART NUMBER") "ERJ-3EKF10R0V") (field (name "MANUFACTURER") "Panasonic"))
      (libsource (lib "") (part "R0603_1"))
    )
    (comp (ref "R34")
      (value "1M")
      (footprint "RESC160X80X55L30N - Full legend")
      (description "Resistor 0603")
      (fields (field (name "PART NUMBER") "ERJ-U03J105V") (field (name "MANUFACTURER") "Panasonic"))
      (libsource (lib "") (part "R0603_3"))
    )
    (comp (ref "R35")
      (value "1k")
      (footprint "RESC160X80X55L30N - Full legend")
      (description "Resistor 0603")
      (fields (field (name "PART NUMBER") "ERJ-3EKF1001V") (field (name "MANUFACTURER") "Panasonic"))
      (libsource (lib "") (part "R0603_3"))
    )
    (comp (ref "R36")
      (value "100")
      (footprint "RESC160X80X55L30N - Full legend")
      (description "Resistor 0603")
      (fields (field (name "PART NUMBER") "ERJ-3EKF1000V") (field (name "MANUFACTURER") "Panasonic"))
      (libsource (lib "") (part "R0603_3"))
    )
    (comp (ref "R37")
      (value "200")
      (footprint "RESC160X80X55L30N - Full legend")
      (description "Resistor 0603")
      (fields (field (name "PART NUMBER") "ERJ-3EKF2000V") (field (name "MANUFACTURER") "Panasonic"))
      (libsource (lib "") (part "R0603_3"))
    )
    (comp (ref "R38")
      (value "1k")
      (footprint "RESC160X80X55L30N - Full legend")
      (description "Resistor 0603")
      (fields (field (name "PART NUMBER") "ERJ-3EKF1001V") (field (name "MANUFACTURER") "Panasonic"))
      (libsource (lib "") (part "R0603_1"))
    )
    (comp (ref "R39")
      (value "1k")
      (footprint "RESC160X80X55L30N - Full legend")
      (description "Resistor 0603")
      (fields (field (name "PART NUMBER") "ERJ-3EKF1001V") (field (name "MANUFACTURER") "Panasonic"))
      (libsource (lib "") (part "R0603_1"))
    )
    (comp (ref "R40")
      (value "100")
      (footprint "RESC160X80X55L30N - Full legend")
      (description "Resistor 0603")
      (fields (field (name "PART NUMBER") "ERJ-3EKF1000V") (field (name "MANUFACTURER") "Panasonic"))
      (libsource (lib "") (part "R0603_1"))
    )
    (comp (ref "R41")
      (value "10k")
      (footprint "RESC160X80X55L30N - Full legend")
      (description "Resistor 0603")
      (fields (field (name "PART NUMBER") "ERJ-3EKF1002V") (field (name "MANUFACTURER") "Panasonic"))
      (libsource (lib "HFPB_01-SchLib") (part "R0603"))
    )
    (comp (ref "R42")
      (value "10k")
      (footprint "RESC160X80X55L30N - Full legend")
      (description "Resistor 0603")
      (fields (field (name "PART NUMBER") "ERJ-3EKF1002V") (field (name "MANUFACTURER") "Panasonic"))
      (libsource (lib "HFPB_01-SchLib") (part "R0603"))
    )
    (comp (ref "R43")
      (value "1k")
      (footprint "RESC160X80X55L30N - Full legend")
      (description "Resistor 0603")
      (fields (field (name "PART NUMBER") "ERJ-3EKF1001V") (field (name "MANUFACTURER") "Panasonic"))
      (libsource (lib "") (part "R0603_1"))
    )
    (comp (ref "R44")
      (value "10k")
      (footprint "RESC160X80X55L30N - Full legend")
      (description "Resistor 0603")
      (fields (field (name "PART NUMBER") "ERJ-3EKF1002V") (field (name "MANUFACTURER") "Panasonic"))
      (libsource (lib "") (part "R0603_1"))
    )
    (comp (ref "R45")
      (value "100")
      (footprint "RESC160X80X55L30N - Full legend")
      (description "Resistor 0603")
      (fields (field (name "PART NUMBER") "ERJ-3EKF1000V") (field (name "MANUFACTURER") "Panasonic"))
      (libsource (lib "") (part "R0603_1"))
    )
    (comp (ref "R46")
      (value "10k")
      (footprint "RESC160X80X55L30N - Full legend")
      (description "Resistor 0603")
      (fields (field (name "PART NUMBER") "ERJ-3EKF1002V") (field (name "MANUFACTURER") "Panasonic"))
      (libsource (lib "HFPB_01-SchLib") (part "R0603"))
    )
    (comp (ref "R47")
      (value "100")
      (footprint "RESC160X80X55L30N - Full legend")
      (description "Resistor 0603")
      (fields (field (name "PART NUMBER") "ERJ-3EKF1000V") (field (name "MANUFACTURER") "Panasonic"))
      (libsource (lib "") (part "R0603_2"))
    )
    (comp (ref "R48")
      (value "1.8k")
      (footprint "RESC160X80X55L30N - Full legend")
      (description "Resistor 0603")
      (fields (field (name "PART NUMBER") "ERJ-3EKF1801V") (field (name "MANUFACTURER") "Panasonic"))
      (libsource (lib "") (part "R0603_1"))
    )
    (comp (ref "R49")
      (value "100")
      (footprint "RESC160X80X55L30N - Full legend")
      (description "Resistor 0603")
      (fields (field (name "PART NUMBER") "ERJ-3EKF1000V") (field (name "MANUFACTURER") "Panasonic"))
      (libsource (lib "HFPB_01-SchLib") (part "R0603"))
    )
    (comp (ref "R50")
      (value "100")
      (footprint "RESC160X80X55L30N - Full legend")
      (description "Resistor 0603")
      (fields (field (name "PART NUMBER") "ERJ-3EKF1000V") (field (name "MANUFACTURER") "Panasonic"))
      (libsource (lib "") (part "R0603_2"))
    )
    (comp (ref "R51")
      (value "200")
      (footprint "RESC160X80X55L30N - Full legend")
      (description "Resistor 0603")
      (fields (field (name "PART NUMBER") "ERJ-3EKF2000V") (field (name "MANUFACTURER") "Panasonic"))
      (libsource (lib "") (part "R0603_2"))
    )
    (comp (ref "R52")
      (value "200")
      (footprint "RESC160X80X55L30N - Full legend")
      (description "Resistor 0603")
      (fields (field (name "PART NUMBER") "ERJ-3EKF2000V") (field (name "MANUFACTURER") "Panasonic"))
      (libsource (lib "") (part "R0603_2"))
    )
    (comp (ref "R53")
      (value "100")
      (footprint "RESC160X80X55L30N - Full legend")
      (description "Resistor 0603")
      (fields (field (name "PART NUMBER") "ERJ-3EKF1000V") (field (name "MANUFACTURER") "Panasonic"))
      (libsource (lib "") (part "R0603_2"))
    )
    (comp (ref "R54")
      (value "10k")
      (footprint "RESC160X80X55L30N - Full legend")
      (description "Resistor 0603")
      (fields (field (name "PART NUMBER") "ERJ-3EKF1002V") (field (name "MANUFACTURER") "Panasonic"))
      (libsource (lib "HFPB_01-SchLib") (part "R0603"))
    )
    (comp (ref "R55")
      (value "1k")
      (footprint "RESC160X80X55L30N - Full legend")
      (description "Resistor 0603")
      (fields (field (name "PART NUMBER") "ERJ-3EKF1001V") (field (name "MANUFACTURER") "Panasonic"))
      (libsource (lib "") (part "R0603_1"))
    )
    (comp (ref "R56")
      (value "200")
      (footprint "RESC160X80X55L30N - Full legend")
      (description "Resistor 0603")
      (fields (field (name "PART NUMBER") "ERJ-3EKF2000V") (field (name "MANUFACTURER") "Panasonic"))
      (libsource (lib "HFPB_01-SchLib") (part "R0603"))
    )
    (comp (ref "R57")
      (value "10k")
      (footprint "RESC160X80X55L30N - Full legend")
      (description "Resistor 0603")
      (fields (field (name "PART NUMBER") "ERJ-3EKF1002V") (field (name "MANUFACTURER") "Panasonic"))
      (libsource (lib "HFPB_01-SchLib") (part "R0603"))
    )
    (comp (ref "R58")
      (value "10k")
      (footprint "RESC160X80X55L30N - Full legend")
      (description "Resistor 0603")
      (fields (field (name "PART NUMBER") "ERJ-3EKF1002V") (field (name "MANUFACTURER") "Panasonic"))
      (libsource (lib "HFPB_01-SchLib") (part "R0603"))
    )
    (comp (ref "R59")
      (value "200")
      (footprint "RESC160X80X55L30N - Full legend")
      (description "Resistor 0603")
      (fields (field (name "PART NUMBER") "ERJ-3EKF2000V") (field (name "MANUFACTURER") "Panasonic"))
      (libsource (lib "HFPB_01-SchLib") (part "R0603"))
    )
    (comp (ref "R60")
      (value "22k")
      (footprint "RESC160X80X55L30N - Full legend")
      (description "Resistor 0603")
      (fields (field (name "PART NUMBER") "ERJ-3EKF2202V") (field (name "MANUFACTURER") "Panasonic"))
      (libsource (lib "") (part "R0603_3"))
    )
    (comp (ref "R61")
      (value "10k")
      (footprint "RESC160X80X55L30N - Full legend")
      (description "Resistor 0603")
      (fields (field (name "PART NUMBER") "ERJ-3EKF1002V") (field (name "MANUFACTURER") "Panasonic"))
      (libsource (lib "") (part "R0603_3"))
    )
    (comp (ref "R62")
      (value "43k")
      (footprint "RESC160X80X55L30N - Full legend")
      (description "Resistor 0603")
      (fields (field (name "PART NUMBER") "ERJ-3EKF4302V") (field (name "MANUFACTURER") "Panasonic"))
      (libsource (lib "") (part "R0603_2"))
    )
    (comp (ref "R63")
      (value "100")
      (footprint "RESC160X80X55L30N - Full legend")
      (description "Resistor 0603")
      (fields (field (name "PART NUMBER") "ERJ-3EKF1000V") (field (name "MANUFACTURER") "Panasonic"))
      (libsource (lib "") (part "R0603_1"))
    )
    (comp (ref "R64")
      (value "100")
      (footprint "RESC160X80X55L30N - Full legend")
      (description "Resistor 0603")
      (fields (field (name "PART NUMBER") "ERJ-3EKF1000V") (field (name "MANUFACTURER") "Panasonic"))
      (libsource (lib "") (part "R0603_3"))
    )
    (comp (ref "R65")
      (value "200")
      (footprint "RESC160X80X55L30N - Full legend")
      (description "Resistor 0603")
      (fields (field (name "PART NUMBER") "ERJ-3EKF2000V") (field (name "MANUFACTURER") "Panasonic"))
      (libsource (lib "") (part "R0603_2"))
    )
    (comp (ref "R66")
      (value "200")
      (footprint "RESC160X80X55L30N - Full legend")
      (description "Resistor 0603")
      (fields (field (name "PART NUMBER") "ERJ-3EKF2000V") (field (name "MANUFACTURER") "Panasonic"))
      (libsource (lib "") (part "R0603_2"))
    )
    (comp (ref "R67")
      (value "100")
      (footprint "RESC160X80X55L30N - Full legend")
      (description "Resistor 0603")
      (fields (field (name "PART NUMBER") "ERJ-3EKF1000V") (field (name "MANUFACTURER") "Panasonic"))
      (libsource (lib "") (part "R0603_2"))
    )
    (comp (ref "R68")
      (value "1k")
      (footprint "RESC160X80X55L30N - Full legend")
      (description "Resistor 0603")
      (fields (field (name "PART NUMBER") "ERJ-3EKF1001V") (field (name "MANUFACTURER") "Panasonic"))
      (libsource (lib "") (part "R0603_1"))
    )
    (comp (ref "R69")
      (value "3.3k")
      (footprint "RESC160X80X55L30N - Full legend")
      (description "Resistor 0603")
      (fields (field (name "PART NUMBER") "ERJ-3EKF3301V") (field (name "MANUFACTURER") "Panasonic"))
      (libsource (lib "") (part "R0603_1"))
    )
    (comp (ref "R70")
      (value "3.3k")
      (footprint "RESC160X80X55L30N - Full legend")
      (description "Resistor 0603")
      (fields (field (name "PART NUMBER") "ERJ-3EKF3301V") (field (name "MANUFACTURER") "Panasonic"))
      (libsource (lib "") (part "R0603_1"))
    )
    (comp (ref "R71")
      (value "3.3k")
      (footprint "RESC160X80X55L30N - Full legend")
      (description "Resistor 0603")
      (fields (field (name "PART NUMBER") "ERJ-3EKF3301V") (field (name "MANUFACTURER") "Panasonic"))
      (libsource (lib "") (part "R0603_1"))
    )
    (comp (ref "R72")
      (value "3.3k")
      (footprint "RESC160X80X55L30N - Full legend")
      (description "Resistor 0603")
      (fields (field (name "PART NUMBER") "ERJ-3EKF3301V") (field (name "MANUFACTURER") "Panasonic"))
      (libsource (lib "") (part "R0603_1"))
    )
    (comp (ref "R73")
      (value "100")
      (footprint "RESC160X80X55L30N - Full legend")
      (description "Resistor 0603")
      (fields (field (name "PART NUMBER") "ERJ-3EKF1000V") (field (name "MANUFACTURER") "Panasonic"))
      (libsource (lib "") (part "R0603_2"))
    )
    (comp (ref "R74")
      (value "1k")
      (footprint "RESC160X80X55L30N - Full legend")
      (description "Resistor 0603")
      (fields (field (name "PART NUMBER") "ERJ-3EKF1001V") (field (name "MANUFACTURER") "Panasonic"))
      (libsource (lib "") (part "R0603_1"))
    )
    (comp (ref "R75")
      (value "1k")
      (footprint "RESC160X80X55L30N - Full legend")
      (description "Resistor 0603")
      (fields (field (name "PART NUMBER") "ERJ-3EKF1001V") (field (name "MANUFACTURER") "Panasonic"))
      (libsource (lib "HFPB_01-SchLib") (part "R0603"))
    )
    (comp (ref "R76")
      (value "10k")
      (footprint "RESC160X80X55L30N - Full legend")
      (description "Resistor 0603")
      (fields (field (name "PART NUMBER") "ERJ-3EKF1002V") (field (name "MANUFACTURER") "Panasonic"))
      (libsource (lib "HFPB_01-SchLib") (part "R0603"))
    )
    (comp (ref "R77")
      (value "10k")
      (footprint "RESC160X80X55L30N - Full legend")
      (description "Resistor 0603")
      (fields (field (name "PART NUMBER") "ERJ-3EKF1002V") (field (name "MANUFACTURER") "Panasonic"))
      (libsource (lib "HFPB_01-SchLib") (part "R0603"))
    )
    (comp (ref "R78")
      (value "10k")
      (footprint "RESC160X80X55L30N - Full legend")
      (description "Resistor 0603")
      (fields (field (name "PART NUMBER") "ERJ-3EKF1002V") (field (name "MANUFACTURER") "Panasonic"))
      (libsource (lib "HFPB_01-SchLib") (part "R0603"))
    )
    (comp (ref "R79")
      (value "10k")
      (footprint "RESC160X80X55L30N - Full legend")
      (description "Resistor 0603")
      (fields (field (name "PART NUMBER") "ERJ-3EKF1002V") (field (name "MANUFACTURER") "Panasonic"))
      (libsource (lib "") (part "R0603_2"))
    )
    (comp (ref "R80")
      (value "10k")
      (footprint "RESC160X80X55L30N - Full legend")
      (description "Resistor 0603")
      (fields (field (name "PART NUMBER") "ERJ-3EKF1002V") (field (name "MANUFACTURER") "Panasonic"))
      (libsource (lib "") (part "R0603_1"))
    )
    (comp (ref "R81")
      (value "10k")
      (footprint "RESC160X80X55L30N - Full legend")
      (description "Resistor 0603")
      (fields (field (name "PART NUMBER") "ERJ-3EKF1002V") (field (name "MANUFACTURER") "Panasonic"))
      (libsource (lib "") (part "R0603_2"))
    )
    (comp (ref "R82")
      (value "100")
      (footprint "RESC160X80X55L30N - Full legend")
      (description "Resistor 0603")
      (fields (field (name "PART NUMBER") "ERJ-3EKF1000V") (field (name "MANUFACTURER") "Panasonic"))
      (libsource (lib "") (part "R0603_2"))
    )
    (comp (ref "R83")
      (value "10k")
      (footprint "RESC160X80X55L30N - Full legend")
      (description "Resistor 0603")
      (fields (field (name "PART NUMBER") "ERJ-3EKF1002V") (field (name "MANUFACTURER") "Panasonic"))
      (libsource (lib "") (part "R0603_2"))
    )
    (comp (ref "R84")
      (value "100")
      (footprint "RESC160X80X55L30N - Full legend")
      (description "Resistor 0603")
      (fields (field (name "PART NUMBER") "ERJ-3EKF1000V") (field (name "MANUFACTURER") "Panasonic"))
      (libsource (lib "") (part "R0603_1"))
    )
    (comp (ref "RT1")
      (value "10k")
      (footprint "NTC - Through hole")
      (description "Thermistor NTC 10k 5%")
      (fields
        (field (name "MANUFACTURER") "TDK-EPCOS")
        (field (name "PART NUMBER") "B57861S0103J040")
        (field (name "VALUE1") "5%")
      )
      (libsource (lib "") (part "B57861S0103J040_1"))
    )
    (comp (ref "RT2")
      (value "10k")
      (footprint "NTC - Through hole")
      (description "Thermistor NTC 10k 5%")
      (fields
        (field (name "MANUFACTURER") "TDK-EPCOS")
        (field (name "PART NUMBER") "B57861S0103J040")
        (field (name "VALUE1") "5%")
      )
      (libsource (lib "") (part "B57861S0103J040_1"))
    )
    (comp (ref "RT3")
      (value "10k")
      (footprint "NTC - Through hole")
      (description "Thermistor NTC 10k 5%")
      (fields
        (field (name "MANUFACTURER") "TDK-EPCOS")
        (field (name "PART NUMBER") "B57861S0103J040")
        (field (name "VALUE1") "5%")
      )
      (libsource (lib "HFPB_01-SchLib") (part "B57861S0103J040"))
    )
    (comp (ref "RT4")
      (value "10k")
      (footprint "NTC - Through hole")
      (description "Thermistor NTC 10k 5%")
      (fields
        (field (name "MANUFACTURER") "TDK-EPCOS")
        (field (name "PART NUMBER") "B57861S0103J040")
        (field (name "VALUE1") "5%")
      )
      (libsource (lib "") (part "B57861S0103J040_1"))
    )
    (comp (ref "SW1")
      (value "EG2208A")
      (footprint "SK22D07")
      (description "Switch ON-ON 0.3A 50V")
      (fields (field (name "MANUFACTURER") "E-Switch") (field (name "ALTIUM_VALUE") "\"text\""))
      (libsource (lib "HFPB_01-SchLib") (part "EG2208A"))
    )
    (comp (ref "TP1")
      (value "NC")
      (footprint "hole/0.8/1.4-R")
      (description "Test point")
      (libsource (lib "HFPB_01-SchLib") (part "TEST POINT"))
    )
    (comp (ref "TP2")
      (value "NC")
      (footprint "hole/0.8/1.4-R")
      (description "Test point")
      (libsource (lib "HFPB_01-SchLib") (part "TEST POINT"))
    )
    (comp (ref "TP3")
      (value "NC")
      (footprint "hole/0.8/1.4-R")
      (description "Test point")
      (libsource (lib "HFPB_01-SchLib") (part "TEST POINT"))
    )
    (comp (ref "TP4")
      (value "GND")
      (footprint "hole/0.8/1.4-R")
      (description "Test point")
      (libsource (lib "HFPB_01-SchLib") (part "TEST POINT"))
    )
    (comp (ref "TP5")
      (value "GND")
      (footprint "hole/0.8/1.4-R")
      (description "Test point")
      (libsource (lib "HFPB_01-SchLib") (part "TEST POINT"))
    )
    (comp (ref "TP6")
      (value "GND")
      (footprint "hole/0.8/1.4-R")
      (description "Test point")
      (libsource (lib "HFPB_01-SchLib") (part "TEST POINT"))
    )
    (comp (ref "U1")
      (value "TSR 1-24120")
      (footprint "SIP800W50P254L1220H1010Q3")
      (description "DC/DC Conv., Non-Iso, 12V, 1A")
      (fields (field (name "MANUFACTURER") "Traco Power"))
      (libsource (lib "HFPB_01-SchLib") (part "TSR 1-24120"))
    )
    (comp (ref "U2")
      (value "TSR 1-2450")
      (footprint "SIP800W50P254L1220H1010Q3")
      (description "DC/DC Conv., Non-Iso, 5.0V, 1A")
      (fields (field (name "MANUFACTURER") "Traco Power"))
      (libsource (lib "HFPB_01-SchLib") (part "TSR 1-2450"))
    )
    (comp (ref "U3")
      (value "LD39050PU33R")
      (footprint "SON7P95_300X300X100L40X35T235X165N")
      (description "LDO 3.3V 500mA")
      (fields (field (name "MANUFACTURER") "STM"))
      (libsource (lib "HFPB_01-SchLib") (part "LD39050PU33R"))
    )
    (comp (ref "U4")
      (value "STM32F334R8T7")
      (footprint "QFP64P50_1200X1200X160L60X22N")
      (description "ARM Cortex-M4+ STM32F3 Microcontroller IC 32-Bit 72MHz 64KB")
      (fields (field (name "MANUFACTURER") "STMicroelectronics") (field (name "PACKAGE/CASE") "LQFP-64"))
      (libsource (lib "HFPB_01-SchLib") (part "STM32F334R8T7"))
    )
    (comp (ref "U5")
      (value "AD8628AUJZ")
      (footprint "SOT23-5P95_280X145L45X40N")
      (description "OpAmp Rail-to-Rail 1 Channel")
      (fields (field (name "MANUFACTURER") "Analog Devices") (field (name "PACKAGE/CASE") "TSOT23-5"))
      (libsource (lib "HFPB_01-SchLib") (part "AD8628AUJZ"))
    )
    (comp (ref "U6")
      (value "CP2102-GM")
      (footprint "QFN29P50_500X500X100L55X23T315N")
      (description "Interface USB to UART")
      (fields (field (name "MANUFACTURER") "Silicon Labs") (field (name "PACKAGE/CASE") "QFN-28"))
      (libsource (lib "HFPB_01-SchLib") (part "CP2102-GM"))
    )
    (comp (ref "U7")
      (value "ISO1540D")
      (footprint "SOIC-8")
      (description "Digital Isolator I2C 2500Vrms 2 Channel 1Mbps")
      (fields (field (name "MANUFACTURER") "Silicon Labs"))
      (libsource (lib "HFPB_01-SchLib") (part "ISO1540D"))
    )
    (comp (ref "X1")
      (value "0039281043")
      (footprint "Molex_0039281043")
      (description "Connector Header 4 pin")
      (fields (field (name "MANUFACTURER") "Molex"))
      (libsource (lib "HFPB_01-SchLib") (part "0353170420"))
    )
    (comp (ref "X2")
      (value "WF-2R")
      (footprint "WF-02MR")
      (description "Connector 2 pin, Right angle, 2.54mm")
      (fields (field (name "MANUFACTURER") "Connfly"))
      (libsource (lib "HFPB_01-SchLib") (part "WF-2R"))
    )
    (comp (ref "X3")
      (value "SMA-J-P-H-RA-TH1")
      (footprint "Samtec_SMA-J-P-H-RA-TH1")
      (description "SMA Jack, Socket, Right Angle 50Ohm")
      (fields (field (name "MANUFACTURER") "Samtec"))
      (libsource (lib "HFPB_01-SchLib") (part "SMA-J-P-H-RA-TH1"))
    )
    (comp (ref "X4")
      (value "WF-2R")
      (footprint "WF-02MR")
      (description "Connector 2 pin, Right angle, 2.54mm")
      (fields (field (name "MANUFACTURER") "Connfly"))
      (libsource (lib "HFPB_01-SchLib") (part "WF-2R"))
    )
    (comp (ref "X5")
      (value "SMA-J-P-H-RA-TH1")
      (footprint "Samtec_SMA-J-P-H-RA-TH1")
      (description "SMA Jack, Socket, Right Angle 50Ohm")
      (fields (field (name "MANUFACTURER") "Samtec"))
      (libsource (lib "HFPB_01-SchLib") (part "SMA-J-P-H-RA-TH1"))
    )
    (comp (ref "X6")
      (value "1074")
      (footprint "Keystone-1074")
      (description "Battery holder for CR2032")
      (fields (field (name "MANUFACTURER") "Keystone"))
      (libsource (lib "HFPB_01-SchLib") (part "1074"))
    )
    (comp (ref "X7")
      (value "SWD")
      (footprint "PLS-5")
      (description "Connector 5 holes 2mm")
      (libsource (lib "HFPB_01-SchLib") (part "CONNECTOR-5 (2mm)"))
    )
    (comp (ref "X8")
      (value "SS-52400-003")
      (footprint "BELFUSE_SS-52400-003")
      (description "USB Type-C, Right Angle Receptacle 24 Position")
      (fields (field (name "MANUFACTURER") "Stewart"))
      (libsource (lib "HFPB_01-SchLib") (part "SS-52400-003"))
    )
    (comp (ref "X9")
      (value "B04B-PASK-1(LF)(SN)")
      (footprint "JST_B04B-PASK-1")
      (description "Connector Header 4 pins, 2.0mm")
      (fields (field (name "MANUFACTURER") "JST"))
      (libsource (lib "HFPB_01-SchLib") (part "B04B-PASK-1(LF)(SN)"))
    )
    (comp (ref "Y1")
      (value "8MHz")
      (footprint "XTAL1140X470X430D1310L435X63N")
      (description "Crystal 8MHz")
      (fields (field (name "PART NUMBER") "ECS-80-20-5PX-TR") (field (name "MANUFACTURER") "ECS Inc."))
      (libsource (lib "HFPB_01-SchLib") (part "ECS-80-20-5PX-TR"))
    )
  )
  (nets
    (net (code "1") (name "+(15-30)V") (class "Default")
      (node (ref "C2") (pin "1") (pinfunction "1_1") (pintype "passive"))
      (node (ref "C3") (pin "1") (pinfunction "1_1") (pintype "passive"))
      (node (ref "C5") (pin "P") (pinfunction "P_P") (pintype "passive"))
      (node (ref "C6") (pin "P") (pinfunction "P_P") (pintype "passive"))
      (node (ref "C8") (pin "1") (pinfunction "1_1") (pintype "passive"))
      (node (ref "C9") (pin "1") (pinfunction "1_1") (pintype "passive"))
      (node (ref "D2") (pin "C") (pinfunction "C_C") (pintype "passive"))
      (node (ref "U1") (pin "1") (pinfunction "VIN_1") (pintype "power_in"))
      (node (ref "U2") (pin "1") (pinfunction "VIN_1") (pintype "power_in"))
      (node (ref "X1") (pin "1") (pinfunction "1_1") (pintype "passive"))
      (node (ref "X1") (pin "3") (pinfunction "3_3") (pintype "passive"))
    )
    (net (code "2") (name "+3.3V") (class "Default")
      (node (ref "BU2") (pin "3") (pinfunction "3_3") (pintype "passive"))
      (node (ref "BU2") (pin "4") (pinfunction "4_4") (pintype "passive"))
      (node (ref "C18") (pin "1") (pinfunction "1_1") (pintype "passive"))
      (node (ref "C21") (pin "1") (pinfunction "1_1") (pintype "passive"))
      (node (ref "C22") (pin "1") (pinfunction "1_1") (pintype "passive"))
      (node (ref "C23") (pin "1") (pinfunction "1_1") (pintype "passive"))
      (node (ref "C24") (pin "1") (pinfunction "1_1") (pintype "passive"))
      (node (ref "C25") (pin "1") (pinfunction "1_1") (pintype "passive"))
      (node (ref "C31") (pin "1") (pinfunction "1_1") (pintype "passive"))
      (node (ref "C36") (pin "1") (pinfunction "1_1") (pintype "passive"))
      (node (ref "FB4") (pin "1") (pinfunction "1_1") (pintype "passive"))
      (node (ref "LS1") (pin "P") (pinfunction "P_P") (pintype "passive"))
      (node (ref "Q2") (pin "4") (pinfunction "S2_4") (pintype "passive"))
      (node (ref "Q4") (pin "4") (pinfunction "S2_4") (pintype "passive"))
      (node (ref "R18") (pin "2") (pinfunction "2_2") (pintype "passive"))
      (node (ref "R19") (pin "1") (pinfunction "1_1") (pintype "passive"))
      (node (ref "R34") (pin "1") (pinfunction "1_1") (pintype "passive"))
      (node (ref "R42") (pin "2") (pinfunction "2_2") (pintype "passive"))
      (node (ref "R46") (pin "2") (pinfunction "2_2") (pintype "passive"))
      (node (ref "R56") (pin "2") (pinfunction "2_2") (pintype "passive"))
      (node (ref "R57") (pin "2") (pinfunction "2_2") (pintype "passive"))
      (node (ref "R58") (pin "2") (pinfunction "2_2") (pintype "passive"))
      (node (ref "R59") (pin "2") (pinfunction "2_2") (pintype "passive"))
      (node (ref "R71") (pin "2") (pinfunction "2_2") (pintype "passive"))
      (node (ref "R72") (pin "2") (pinfunction "2_2") (pintype "passive"))
      (node (ref "R76") (pin "2") (pinfunction "2_2") (pintype "passive"))
      (node (ref "R77") (pin "2") (pinfunction "2_2") (pintype "passive"))
      (node (ref "R78") (pin "2") (pinfunction "2_2") (pintype "passive"))
      (node (ref "R80") (pin "2") (pinfunction "2_2") (pintype "passive"))
      (node (ref "U3") (pin "4") (pinfunction "VOUT_4") (pintype "power_in"))
      (node (ref "U4") (pin "19") (pinfunction "VDD_19") (pintype "passive"))
      (node (ref "U4") (pin "32") (pinfunction "VDD_32") (pintype "power_in"))
      (node (ref "U4") (pin "48") (pinfunction "VDD_48") (pintype "power_in"))
      (node (ref "U4") (pin "64") (pinfunction "VDD_64") (pintype "power_in"))
      (node (ref "U5") (pin "5") (pinfunction "V+_5") (pintype "power_in"))
      (node (ref "U7") (pin "1") (pinfunction "Vcc1_1") (pintype "power_in"))
      (node (ref "X7") (pin "1") (pinfunction "1_1") (pintype "passive"))
    )
    (net (code "3") (name "+3.3V'") (class "Default")
      (node (ref "Q2") (pin "3") (pinfunction "D2_3") (pintype "passive"))
      (node (ref "R17") (pin "1") (pinfunction "1_1") (pintype "passive"))
      (node (ref "R20") (pin "2") (pinfunction "2_2") (pintype "passive"))
    )
    (net (code "4") (name "+3.3VA") (class "Default")
      (node (ref "C28") (pin "1") (pinfunction "1_1") (pintype "passive"))
      (node (ref "C29") (pin "1") (pinfunction "1_1") (pintype "passive"))
      (node (ref "FB4") (pin "2") (pinfunction "2_2") (pintype "passive"))
      (node (ref "R2") (pin "2") (pinfunction "2_2") (pintype "passive"))
      (node (ref "R22") (pin "2") (pinfunction "2_2") (pintype "passive"))
      (node (ref "R74") (pin "2") (pinfunction "2_2") (pintype "passive"))
      (node (ref "R75") (pin "2") (pinfunction "2_2") (pintype "passive"))
      (node (ref "U4") (pin "13") (pinfunction "VDDA_13") (pintype "power_in"))
    )
    (net (code "5") (name "+5.0V") (class "Default")
      (node (ref "C11") (pin "P") (pinfunction "P_P") (pintype "passive"))
      (node (ref "C12") (pin "1") (pinfunction "1_1") (pintype "passive"))
      (node (ref "C34") (pin "1") (pinfunction "1_1") (pintype "passive"))
      (node (ref "C35") (pin "1") (pinfunction "1_1") (pintype "passive"))
      (node (ref "D4") (pin "A") (pinfunction "A_A") (pintype "passive"))
      (node (ref "FB2") (pin "1") (pinfunction "1_1") (pintype "passive"))
      (node (ref "R69") (pin "2") (pinfunction "2_2") (pintype "passive"))
      (node (ref "R70") (pin "2") (pinfunction "2_2") (pintype "passive"))
      (node (ref "U7") (pin "8") (pinfunction "Vcc2_8") (pintype "power_in"))
      (node (ref "X9") (pin "4") (pinfunction "4_4") (pintype "passive"))
    )
    (net (code "6") (name "+5.0V_USB") (class "Default")
      (node (ref "C37") (pin "2") (pinfunction "2_2") (pintype "passive"))
      (node (ref "C38") (pin "1") (pinfunction "1_1") (pintype "passive"))
      (node (ref "D3") (pin "A") (pinfunction "A_A") (pintype "passive"))
      (node (ref "FB5") (pin "2") (pinfunction "2_2") (pintype "passive"))
      (node (ref "R60") (pin "1") (pinfunction "1_1") (pintype "passive"))
      (node (ref "R61") (pin "1") (pinfunction "1_1") (pintype "passive"))
      (node (ref "U6") (pin "7") (pinfunction "REGIN_7") (pintype "power_in"))
    )
    (net (code "7") (name "+12V") (class "Default")
      (node (ref "C1") (pin "1") (pinfunction "1_1") (pintype "passive"))
      (node (ref "C14") (pin "1") (pinfunction "1_1") (pintype "passive"))
      (node (ref "D1") (pin "C") (pinfunction "C_C") (pintype "passive"))
      (node (ref "D7") (pin "C") (pinfunction "C_C") (pintype "passive"))
      (node (ref "FB1") (pin "1") (pinfunction "1_1") (pintype "passive"))
      (node (ref "X2") (pin "2") (pinfunction "2_2") (pintype "passive"))
      (node (ref "X4") (pin "2") (pinfunction "2_2") (pintype "passive"))
    )
    (net (code "8") (name "+HV") (class "Default")
      (node (ref "R1") (pin "2") (pinfunction "2_2") (pintype "passive"))
    )
    (net (code "9") (name "+VBAT") (class "Default")
      (node (ref "C27") (pin "1") (pinfunction "1_1") (pintype "passive"))
      (node (ref "U4") (pin "1") (pinfunction "VBAT_1") (pintype "passive"))
      (node (ref "X6") (pin "2") (pinfunction "PLUS_2") (pintype "passive"))
    )
    (net (code "10") (name "/ADC_Current") (class "Default")
      (node (ref "C30") (pin "1") (pinfunction "1_1") (pintype "passive"))
      (node (ref "R43") (pin "1") (pinfunction "1_1") (pintype "passive"))
      (node (ref "U4") (pin "17") (pinfunction "PA3_17") (pintype "bidirectional"))
    )
    (net (code "11") (name "/ADC_HV") (class "Default")
      (node (ref "C13") (pin "1") (pinfunction "1_1") (pintype "passive"))
      (node (ref "D5") (pin "C") (pinfunction "Cathode_C") (pintype "passive"))
      (node (ref "R11") (pin "1") (pinfunction "1_1") (pintype "passive"))
      (node (ref "R14") (pin "2") (pinfunction "2_2") (pintype "passive"))
      (node (ref "U4") (pin "14") (pinfunction "PA0_14") (pintype "bidirectional"))
    )
    (net (code "12") (name "/ADC_NTC1") (class "Default")
      (node (ref "C19") (pin "1") (pinfunction "1_1") (pintype "passive"))
      (node (ref "R22") (pin "1") (pinfunction "1_1") (pintype "passive"))
      (node (ref "RT2") (pin "2") (pinfunction "2_2") (pintype "passive"))
      (node (ref "U4") (pin "15") (pinfunction "PA1_15") (pintype "bidirectional"))
    )
    (net (code "13") (name "/ADC_NTC2") (class "Default")
      (node (ref "C7") (pin "1") (pinfunction "1_1") (pintype "passive"))
      (node (ref "R2") (pin "1") (pinfunction "1_1") (pintype "passive"))
      (node (ref "RT1") (pin "2") (pinfunction "2_2") (pintype "passive"))
      (node (ref "U4") (pin "16") (pinfunction "PA2_16") (pintype "bidirectional"))
    )
    (net (code "14") (name "/ADC_NTC3") (class "Default")
      (node (ref "C43") (pin "1") (pinfunction "1_1") (pintype "passive"))
      (node (ref "R75") (pin "1") (pinfunction "1_1") (pintype "passive"))
      (node (ref "RT4") (pin "2") (pinfunction "2_2") (pintype "passive"))
      (node (ref "U4") (pin "20") (pinfunction "PA4_20") (pintype "bidirectional"))
    )
    (net (code "15") (name "/ADC_NTC4") (class "Default")
      (node (ref "C45") (pin "1") (pinfunction "1_1") (pintype "passive"))
      (node (ref "R74") (pin "1") (pinfunction "1_1") (pintype "passive"))
      (node (ref "RT3") (pin "2") (pinfunction "2_2") (pintype "passive"))
      (node (ref "U4") (pin "21") (pinfunction "PA5_21") (pintype "bidirectional"))
    )
    (net (code "16") (name "/DANGER") (class "Default")
      (node (ref "R52") (pin "1") (pinfunction "1_1") (pintype "passive"))
      (node (ref "U4") (pin "25") (pinfunction "PC5_25") (pintype "bidirectional"))
    )
    (net (code "17") (name "/DP1_N") (class "Default")
      (node (ref "D9") (pin "2") (pinfunction "IO1_2") (pintype "passive"))
      (node (ref "R73") (pin "1") (pinfunction "1_1") (pintype "passive"))
      (node (ref "X8") (pin "A7") (pinfunction "D-_A7") (pintype "bidirectional"))
      (node (ref "X8") (pin "B7") (pinfunction "D-_B7") (pintype "bidirectional"))
    )
    (net (code "18") (name "/DP1_P") (class "Default")
      (node (ref "D9") (pin "3") (pinfunction "IO2_3") (pintype "passive"))
      (node (ref "R67") (pin "1") (pinfunction "1_1") (pintype "passive"))
      (node (ref "X8") (pin "A6") (pinfunction "D+_A6") (pintype "bidirectional"))
      (node (ref "X8") (pin "B6") (pinfunction "D+_B6") (pintype "bidirectional"))
    )
    (net (code "19") (name "/DP2_N") (class "Default")
      (node (ref "R73") (pin "2") (pinfunction "2_2") (pintype "passive"))
      (node (ref "U6") (pin "5") (pinfunction "D-_5") (pintype "bidirectional"))
    )
    (net (code "20") (name "/DP2_P") (class "Default")
      (node (ref "R67") (pin "2") (pinfunction "2_2") (pintype "passive"))
      (node (ref "U6") (pin "4") (pinfunction "D+_4") (pintype "bidirectional"))
    )
    (net (code "21") (name "/Enc_A") (class "Default")
      (node (ref "C49") (pin "1") (pinfunction "1_1") (pintype "passive"))
      (node (ref "R83") (pin "2") (pinfunction "2_2") (pintype "passive"))
      (node (ref "U4") (pin "42") (pinfunction "PA9_42") (pintype "bidirectional"))
    )
    (net (code "22") (name "/Enc_B") (class "Default")
      (node (ref "C48") (pin "1") (pinfunction "1_1") (pintype "passive"))
      (node (ref "R81") (pin "2") (pinfunction "2_2") (pintype "passive"))
      (node (ref "U4") (pin "41") (pinfunction "PA8_41") (pintype "bidirectional"))
    )
    (net (code "23") (name "/Enc_switch") (class "Default")
      (node (ref "C47") (pin "1") (pinfunction "1_1") (pintype "passive"))
      (node (ref "R79") (pin "2") (pinfunction "2_2") (pintype "passive"))
      (node (ref "U4") (pin "45") (pinfunction "PA12_45") (pintype "bidirectional"))
    )
    (net (code "24") (name "/FAN-ON-1") (class "Default")
      (node (ref "R13") (pin "2") (pinfunction "2_2") (pintype "passive"))
      (node (ref "R8") (pin "1") (pinfunction "1_1") (pintype "passive"))
      (node (ref "U4") (pin "27") (pinfunction "PB1_27") (pintype "bidirectional"))
    )
    (net (code "25") (name "/FAN-ON-2") (class "Default")
      (node (ref "R21") (pin "1") (pinfunction "1_1") (pintype "passive"))
      (node (ref "R28") (pin "2") (pinfunction "2_2") (pintype "passive"))
      (node (ref "U4") (pin "26") (pinfunction "PB0_26") (pintype "bidirectional"))
    )
    (net (code "26") (name "/Gen_Work") (class "Default")
      (node (ref "D6") (pin "C") (pinfunction "Cathode_C") (pintype "passive"))
      (node (ref "R10") (pin "2") (pinfunction "2_2") (pintype "passive"))
      (node (ref "R12") (pin "1") (pinfunction "1_1") (pintype "passive"))
      (node (ref "R15") (pin "2") (pinfunction "2_2") (pintype "passive"))
      (node (ref "R16") (pin "1") (pinfunction "1_1") (pintype "passive"))
      (node (ref "R39") (pin "1") (pinfunction "1_1") (pintype "passive"))
      (node (ref "R9") (pin "1") (pinfunction "1_1") (pintype "passive"))
    )
    (net (code "27") (name "/I2C_SCL") (class "Default")
      (node (ref "R71") (pin "1") (pinfunction "1_1") (pintype "passive"))
      (node (ref "U4") (pin "61") (pinfunction "PB8/I2C_SCL_61") (pintype "bidirectional"))
      (node (ref "U7") (pin "2") (pinfunction "SDA1_2") (pintype "bidirectional"))
    )
    (net (code "28") (name "/I2C_SDA") (class "Default")
      (node (ref "R72") (pin "1") (pinfunction "1_1") (pintype "passive"))
      (node (ref "U4") (pin "62") (pinfunction "PB9/I2C_SDA_62") (pintype "bidirectional"))
      (node (ref "U7") (pin "3") (pinfunction "SCL1_3") (pintype "bidirectional"))
    )
    (net (code "29") (name "/NRST") (class "Default")
      (node (ref "C32") (pin "2") (pinfunction "2_2") (pintype "passive"))
      (node (ref "R53") (pin "2") (pinfunction "2_2") (pintype "passive"))
      (node (ref "R63") (pin "2") (pinfunction "2_2") (pintype "passive"))
      (node (ref "U4") (pin "7") (pinfunction "NRST_7") (pintype "input"))
    )
    (net (code "30") (name "/OUT-DIS") (class "Default")
      (node (ref "C15") (pin "1") (pinfunction "1_1") (pintype "passive"))
      (node (ref "R17") (pin "2") (pinfunction "2_2") (pintype "passive"))
      (node (ref "U4") (pin "3") (pinfunction "PC14/OSC32_IN_3") (pintype "bidirectional"))
    )
    (net (code "31") (name "/PWM_HighLeft_MC") (class "Default")
      (node (ref "R31") (pin "1") (pinfunction "1_1") (pintype "passive"))
      (node (ref "U4") (pin "43") (pinfunction "PA10_43") (pintype "bidirectional"))
    )
    (net (code "32") (name "/PWM_HighRight_MC") (class "Default")
      (node (ref "R5") (pin "1") (pinfunction "1_1") (pintype "passive"))
      (node (ref "U4") (pin "33") (pinfunction "PB12_33") (pintype "bidirectional"))
    )
    (net (code "33") (name "/PWM_LowLeft_MC") (class "Default")
      (node (ref "R10") (pin "1") (pinfunction "1_1") (pintype "passive"))
      (node (ref "U4") (pin "44") (pinfunction "PA11_44") (pintype "bidirectional"))
    )
    (net (code "34") (name "/PWM_LowRight_MC") (class "Default")
      (node (ref "R26") (pin "1") (pinfunction "1_1") (pintype "passive"))
      (node (ref "U4") (pin "34") (pinfunction "PB13_34") (pintype "bidirectional"))
    )
    (net (code "35") (name "/RXD") (class "Default")
      (node (ref "R65") (pin "2") (pinfunction "2_2") (pintype "passive"))
      (node (ref "U4") (pin "59") (pinfunction "PB7/USART1_RX_59") (pintype "bidirectional"))
    )
    (net (code "36") (name "/SND-ON") (class "Default")
      (node (ref "R38") (pin "1") (pinfunction "1_1") (pintype "passive"))
      (node (ref "R41") (pin "2") (pinfunction "2_2") (pintype "passive"))
      (node (ref "U4") (pin "53") (pinfunction "PC12_53") (pintype "bidirectional"))
    )
    (net (code "37") (name "/START{slash}STOP") (class "Default")
      (node (ref "BU4") (pin "3") (pinfunction "3_3") (pintype "passive"))
      (node (ref "BU4") (pin "4") (pinfunction "4_4") (pintype "passive"))
      (node (ref "R80") (pin "1") (pinfunction "1_1") (pintype "passive"))
      (node (ref "R82") (pin "1") (pinfunction "1_1") (pintype "passive"))
      (node (ref "U4") (pin "4") (pinfunction "PC15/OSC32_OUT_4") (pintype "bidirectional"))
    )
    (net (code "38") (name "/SWCLK") (class "Default")
      (node (ref "R47") (pin "2") (pinfunction "2_2") (pintype "passive"))
      (node (ref "U4") (pin "49") (pinfunction "PA14/SWCLK_49") (pintype "bidirectional"))
    )
    (net (code "39") (name "/SWDIO") (class "Default")
      (node (ref "R50") (pin "2") (pinfunction "2_2") (pintype "passive"))
      (node (ref "U4") (pin "46") (pinfunction "PA13/SWDAT_46") (pintype "bidirectional"))
    )
    (net (code "40") (name "/TXD") (class "Default")
      (node (ref "LD6") (pin "C") (pinfunction "C_C") (pintype "passive"))
      (node (ref "R57") (pin "1") (pinfunction "1_1") (pintype "passive"))
      (node (ref "R66") (pin "2") (pinfunction "2_2") (pintype "passive"))
      (node (ref "U4") (pin "58") (pinfunction "PB6/USART1_TX_58") (pintype "bidirectional"))
    )
    (net (code "41") (name "/USB-PC") (class "Default")
      (node (ref "C40") (pin "1") (pinfunction "1_1") (pintype "passive"))
      (node (ref "R68") (pin "1") (pinfunction "1_1") (pintype "passive"))
      (node (ref "U4") (pin "2") (pinfunction "PC13_2") (pintype "bidirectional"))
    )
    (net (code "42") (name "/VBUS") (class "Default")
      (node (ref "C33") (pin "1") (pinfunction "1_1") (pintype "passive"))
      (node (ref "D9") (pin "4") (pinfunction "VCC_4") (pintype "passive"))
      (node (ref "FB5") (pin "1") (pinfunction "1_1") (pintype "passive"))
      (node (ref "X8") (pin "A4") (pinfunction "VBUS_A4") (pintype "passive"))
      (node (ref "X8") (pin "A9") (pinfunction "VBUS_A9") (pintype "power_in"))
      (node (ref "X8") (pin "B4") (pinfunction "VBUS_B4") (pintype "power_in"))
      (node (ref "X8") (pin "B9") (pinfunction "VBUS_B9") (pintype "power_in"))
    )
    (net (code "43") (name "/Warning") (class "Default")
      (node (ref "R51") (pin "1") (pinfunction "1_1") (pintype "passive"))
      (node (ref "U4") (pin "24") (pinfunction "PC4_24") (pintype "bidirectional"))
    )
    (net (code "44") (name "Current_Sense") (class "Default")
      (node (ref "R45") (pin "2") (pinfunction "2_2") (pintype "passive"))
    )
    (net (code "45") (name "ENABLE") (class "Default")
      (node (ref "R55") (pin "1") (pinfunction "1_1") (pintype "passive"))
      (node (ref "U4") (pin "56") (pinfunction "PB4_56") (pintype "bidirectional"))
    )
    (net (code "46") (name "GND") (class "Default")
      (node (ref "BR1") (pin "0") (pinfunction "SHIELD_0") (pintype "passive"))
      (node (ref "BR1") (pin "C") (pinfunction "C_C") (pintype "passive"))
      (node (ref "BR1") (pin "W") (pinfunction "W_W") (pintype "passive"))
      (node (ref "BU1") (pin "1") (pinfunction "1_1") (pintype "passive"))
      (node (ref "BU1") (pin "2") (pinfunction "2_2") (pintype "passive"))
      (node (ref "BU3") (pin "1") (pinfunction "1_1") (pintype "passive"))
      (node (ref "BU3") (pin "2") (pinfunction "2_2") (pintype "passive"))
      (node (ref "BU4") (pin "1") (pinfunction "1_1") (pintype "passive"))
      (node (ref "BU4") (pin "2") (pinfunction "2_2") (pintype "passive"))
      (node (ref "C1") (pin "2") (pinfunction "2_2") (pintype "passive"))
      (node (ref "C10") (pin "2") (pinfunction "2_2") (pintype "passive"))
      (node (ref "C11") (pin "N") (pinfunction "N_N") (pintype "passive"))
      (node (ref "C12") (pin "2") (pinfunction "2_2") (pintype "passive"))
      (node (ref "C13") (pin "2") (pinfunction "2_2") (pintype "passive"))
      (node (ref "C14") (pin "2") (pinfunction "2_2") (pintype "passive"))
      (node (ref "C15") (pin "2") (pinfunction "2_2") (pintype "passive"))
      (node (ref "C16") (pin "2") (pinfunction "2_2") (pintype "passive"))
      (node (ref "C17") (pin "2") (pinfunction "2_2") (pintype "passive"))
      (node (ref "C18") (pin "2") (pinfunction "2_2") (pintype "passive"))
      (node (ref "C19") (pin "2") (pinfunction "2_2") (pintype "passive"))
      (node (ref "C2") (pin "2") (pinfunction "2_2") (pintype "passive"))
      (node (ref "C20") (pin "2") (pinfunction "2_2") (pintype "passive"))
      (node (ref "C21") (pin "2") (pinfunction "2_2") (pintype "passive"))
      (node (ref "C22") (pin "2") (pinfunction "2_2") (pintype "passive"))
      (node (ref "C23") (pin "2") (pinfunction "2_2") (pintype "passive"))
      (node (ref "C24") (pin "2") (pinfunction "2_2") (pintype "passive"))
      (node (ref "C25") (pin "2") (pinfunction "2_2") (pintype "passive"))
      (node (ref "C26") (pin "2") (pinfunction "2_2") (pintype "passive"))
      (node (ref "C27") (pin "2") (pinfunction "2_2") (pintype "passive"))
      (node (ref "C28") (pin "2") (pinfunction "2_2") (pintype "passive"))
      (node (ref "C29") (pin "2") (pinfunction "2_2") (pintype "passive"))
      (node (ref "C3") (pin "2") (pinfunction "2_2") (pintype "passive"))
      (node (ref "C30") (pin "2") (pinfunction "2_2") (pintype "passive"))
      (node (ref "C31") (pin "2") (pinfunction "2_2") (pintype "passive"))
      (node (ref "C32") (pin "1") (pinfunction "1_1") (pintype "passive"))
      (node (ref "C33") (pin "2") (pinfunction "2_2") (pintype "passive"))
      (node (ref "C34") (pin "2") (pinfunction "2_2") (pintype "passive"))
      (node (ref "C35") (pin "2") (pinfunction "2_2") (pintype "passive"))
      (node (ref "C36") (pin "2") (pinfunction "2_2") (pintype "passive"))
      (node (ref "C37") (pin "1") (pinfunction "1_1") (pintype "passive"))
      (node (ref "C38") (pin "2") (pinfunction "2_2") (pintype "passive"))
      (node (ref "C39") (pin "1") (pinfunction "1_1") (pintype "passive"))
      (node (ref "C4") (pin "2") (pinfunction "2_2") (pintype "passive"))
      (node (ref "C40") (pin "2") (pinfunction "2_2") (pintype "passive"))
      (node (ref "C41") (pin "2") (pinfunction "2_2") (pintype "passive"))
      (node (ref "C42") (pin "2") (pinfunction "2_2") (pintype "passive"))
      (node (ref "C43") (pin "2") (pinfunction "2_2") (pintype "passive"))
      (node (ref "C44") (pin "2") (pinfunction "2_2") (pintype "passive"))
      (node (ref "C45") (pin "2") (pinfunction "2_2") (pintype "passive"))
      (node (ref "C46") (pin "2") (pinfunction "2_2") (pintype "passive"))
      (node (ref "C47") (pin "2") (pinfunction "2_2") (pintype "passive"))
      (node (ref "C48") (pin "2") (pinfunction "2_2") (pintype "passive"))
      (node (ref "C49") (pin "2") (pinfunction "2_2") (pintype "passive"))
      (node (ref "C5") (pin "N") (pinfunction "N_N") (pintype "passive"))
      (node (ref "C6") (pin "N") (pinfunction "N_N") (pintype "passive"))
      (node (ref "C7") (pin "2") (pinfunction "2_2") (pintype "passive"))
      (node (ref "C8") (pin "2") (pinfunction "2_2") (pintype "passive"))
      (node (ref "C9") (pin "2") (pinfunction "2_2") (pintype "passive"))
      (node (ref "D2") (pin "A") (pinfunction "A_A") (pintype "passive"))
      (node (ref "D5") (pin "A") (pinfunction "Anode_A") (pintype "passive"))
      (node (ref "D6") (pin "A") (pinfunction "Anode_A") (pintype "passive"))
      (node (ref "D8") (pin "A") (pinfunction "Anode_A") (pintype "passive"))
      (node (ref "D9") (pin "1") (pinfunction "GND_1") (pintype "passive"))
      (node (ref "LD1") (pin "C") (pinfunction "C_C") (pintype "passive"))
      (node (ref "LD2") (pin "C") (pinfunction "C_C") (pintype "passive"))
      (node (ref "LD3") (pin "C") (pinfunction "C_C") (pintype "passive"))
      (node (ref "LD4") (pin "C") (pinfunction "C_C") (pintype "passive"))
      (node (ref "Q1") (pin "2") (pinfunction "S_2") (pintype "passive"))
      (node (ref "Q2") (pin "1") (pinfunction "S1_1") (pintype "passive"))
      (node (ref "Q3") (pin "2") (pinfunction "S_2") (pintype "passive"))
      (node (ref "Q4") (pin "1") (pinfunction "S1_1") (pintype "passive"))
      (node (ref "Q5") (pin "2") (pinfunction "S_2") (pintype "passive"))
      (node (ref "R13") (pin "1") (pinfunction "1_1") (pintype "passive"))
      (node (ref "R14") (pin "1") (pinfunction "1_1") (pintype "passive"))
      (node (ref "R16") (pin "2") (pinfunction "2_2") (pintype "passive"))
      (node (ref "R23") (pin "1") (pinfunction "1_1") (pintype "passive"))
      (node (ref "R28") (pin "1") (pinfunction "1_1") (pintype "passive"))
      (node (ref "R29") (pin "2") (pinfunction "2_2") (pintype "passive"))
      (node (ref "R3") (pin "1") (pinfunction "1_1") (pintype "passive"))
      (node (ref "R35") (pin "2") (pinfunction "2_2") (pintype "passive"))
      (node (ref "R41") (pin "1") (pinfunction "1_1") (pintype "passive"))
      (node (ref "R44") (pin "1") (pinfunction "1_1") (pintype "passive"))
      (node (ref "R49") (pin "1") (pinfunction "1_1") (pintype "passive"))
      (node (ref "R54") (pin "1") (pinfunction "1_1") (pintype "passive"))
      (node (ref "R55") (pin "2") (pinfunction "2_2") (pintype "passive"))
      (node (ref "R62") (pin "2") (pinfunction "2_2") (pintype "passive"))
      (node (ref "R84") (pin "2") (pinfunction "2_2") (pintype "passive"))
      (node (ref "RT1") (pin "1") (pinfunction "1_1") (pintype "passive"))
      (node (ref "RT2") (pin "1") (pinfunction "1_1") (pintype "passive"))
      (node (ref "RT3") (pin "1") (pinfunction "1_1") (pintype "passive"))
      (node (ref "RT4") (pin "1") (pinfunction "1_1") (pintype "passive"))
      (node (ref "TP4") (pin "1") (pinfunction "1_1") (pintype "passive"))
      (node (ref "TP5") (pin "1") (pinfunction "1_1") (pintype "passive"))
      (node (ref "TP6") (pin "1") (pinfunction "1_1") (pintype "passive"))
      (node (ref "U1") (pin "2") (pinfunction "GND_2") (pintype "power_in"))
      (node (ref "U2") (pin "2") (pinfunction "GND_2") (pintype "power_in"))
      (node (ref "U3") (pin "2") (pinfunction "GND_2") (pintype "power_in"))
      (node (ref "U3") (pin "EP") (pinfunction "GND_EP") (pintype "power_in"))
      (node (ref "U4") (pin "12") (pinfunction "VSSA_12") (pintype "power_in"))
      (node (ref "U4") (pin "18") (pinfunction "VSS_18") (pintype "power_in"))
      (node (ref "U4") (pin "31") (pinfunction "VSS_31") (pintype "power_in"))
      (node (ref "U4") (pin "47") (pinfunction "VSS_47") (pintype "power_in"))
      (node (ref "U4") (pin "63") (pinfunction "VSS_63") (pintype "power_in"))
      (node (ref "U5") (pin "2") (pinfunction "V-_2") (pintype "power_in"))
      (node (ref "U6") (pin "3") (pinfunction "GND_3") (pintype "power_in"))
      (node (ref "U6") (pin "EP") (pinfunction "GND_EP") (pintype "power_in"))
      (node (ref "U7") (pin "4") (pinfunction "Gnd1_4") (pintype "power_in"))
      (node (ref "U7") (pin "5") (pinfunction "Gnd2_5") (pintype "power_in"))
      (node (ref "X1") (pin "2") (pinfunction "2_2") (pintype "passive"))
      (node (ref "X1") (pin "4") (pinfunction "4_4") (pintype "passive"))
      (node (ref "X3") (pin "2") (pinfunction "2_2") (pintype "passive"))
      (node (ref "X5") (pin "2") (pinfunction "2_2") (pintype "passive"))
      (node (ref "X6") (pin "1") (pinfunction "MINUS_1") (pintype "passive"))
      (node (ref "X7") (pin "3") (pinfunction "3_3") (pintype "passive"))
      (node (ref "X8") (pin "A1") (pinfunction "GND_A1") (pintype "power_in"))
      (node (ref "X8") (pin "A12") (pinfunction "GND_A12") (pintype "power_in"))
      (node (ref "X8") (pin "B1") (pinfunction "GND_B1") (pintype "power_in"))
      (node (ref "X8") (pin "B12") (pinfunction "GND_B12") (pintype "power_in"))
      (node (ref "X8") (pin "G1") (pinfunction "GND/SHIELD_G1") (pintype "power_in"))
      (node (ref "X8") (pin "G2") (pinfunction "GND/SHIELD_G2") (pintype "power_in"))
      (node (ref "X8") (pin "G3") (pinfunction "GND/SHIELD_G3") (pintype "power_in"))
      (node (ref "X8") (pin "G4") (pinfunction "GND/SHIELD_G4") (pintype "power_in"))
      (node (ref "X8") (pin "S1") (pinfunction "GND/SHIELD_S1") (pintype "power_in"))
      (node (ref "X8") (pin "S2") (pinfunction "GND/SHIELD_S2") (pintype "power_in"))
      (node (ref "X8") (pin "S3") (pinfunction "GND/SHIELD_S3") (pintype "power_in"))
      (node (ref "X8") (pin "S4") (pinfunction "GND/SHIELD_S4") (pintype "power_in"))
      (node (ref "X9") (pin "3") (pinfunction "3_3") (pintype "passive"))
    )
    (net (code "47") (name "Net-(BR1-PadA)") (class "Default")
      (node (ref "BR1") (pin "A") (pinfunction "A_A") (pintype "passive"))
      (node (ref "R78") (pin "1") (pinfunction "1_1") (pintype "passive"))
      (node (ref "R83") (pin "1") (pinfunction "1_1") (pintype "passive"))
    )
    (net (code "48") (name "Net-(BR1-PadB)") (class "Default")
      (node (ref "BR1") (pin "B") (pinfunction "B_B") (pintype "passive"))
      (node (ref "R77") (pin "1") (pinfunction "1_1") (pintype "passive"))
      (node (ref "R81") (pin "1") (pinfunction "1_1") (pintype "passive"))
    )
    (net (code "49") (name "Net-(BR1-PadS)") (class "Default")
      (node (ref "BR1") (pin "S") (pinfunction "S_S") (pintype "passive"))
      (node (ref "R76") (pin "1") (pinfunction "1_1") (pintype "passive"))
      (node (ref "R79") (pin "1") (pinfunction "1_1") (pintype "passive"))
    )
    (net (code "50") (name "Net-(BU2-Pad1)") (class "Default")
      (node (ref "BU2") (pin "1") (pinfunction "1_1") (pintype "passive"))
      (node (ref "BU2") (pin "2") (pinfunction "2_2") (pintype "passive"))
      (node (ref "R40") (pin "2") (pinfunction "2_2") (pintype "passive"))
    )
    (net (code "51") (name "Net-(BU3-Pad3)") (class "Default")
      (node (ref "BU3") (pin "3") (pinfunction "3_3") (pintype "passive"))
      (node (ref "BU3") (pin "4") (pinfunction "4_4") (pintype "passive"))
      (node (ref "R63") (pin "1") (pinfunction "1_1") (pintype "passive"))
    )
    (net (code "52") (name "Net-(C20-Pad1)") (class "Default")
      (node (ref "C20") (pin "1") (pinfunction "1_1") (pintype "passive"))
      (node (ref "R25") (pin "2") (pinfunction "2_2") (pintype "passive"))
    )
    (net (code "53") (name "Net-(C42-Pad1)") (class "Default")
      (node (ref "C42") (pin "1") (pinfunction "1_1") (pintype "passive"))
      (node (ref "R64") (pin "1") (pinfunction "1_1") (pintype "passive"))
      (node (ref "Y1") (pin "2") (pinfunction "2_2") (pintype "passive"))
    )
    (net (code "54") (name "Net-(C46-Pad1)") (class "Default")
      (node (ref "C46") (pin "1") (pinfunction "1_1") (pintype "passive"))
      (node (ref "R82") (pin "2") (pinfunction "2_2") (pintype "passive"))
    )
    (net (code "55") (name "Net-(D3-PadC)") (class "Default")
      (node (ref "D3") (pin "C") (pinfunction "C_C") (pintype "passive"))
      (node (ref "D4") (pin "C") (pinfunction "C_C") (pintype "passive"))
      (node (ref "FB3") (pin "2") (pinfunction "2_2") (pintype "passive"))
    )
    (net (code "56") (name "Net-(D8-Cathode)") (class "Default")
      (node (ref "D8") (pin "C") (pinfunction "Cathode_C") (pintype "passive"))
      (node (ref "R30") (pin "1") (pinfunction "1_1") (pintype "passive"))
      (node (ref "R31") (pin "2") (pinfunction "2_2") (pintype "passive"))
      (node (ref "R32") (pin "1") (pinfunction "1_1") (pintype "passive"))
      (node (ref "R33") (pin "2") (pinfunction "2_2") (pintype "passive"))
      (node (ref "R35") (pin "1") (pinfunction "1_1") (pintype "passive"))
    )
    (net (code "57") (name "Net-(LD1-PadA)") (class "Default")
      (node (ref "LD1") (pin "A") (pinfunction "A_A") (pintype "passive"))
      (node (ref "R19") (pin "2") (pinfunction "2_2") (pintype "passive"))
    )
    (net (code "58") (name "Net-(LD2-PadA)") (class "Default")
      (node (ref "LD2") (pin "A") (pinfunction "A_A") (pintype "passive"))
      (node (ref "R37") (pin "2") (pinfunction "2_2") (pintype "passive"))
    )
    (net (code "59") (name "Net-(LD3-PadA)") (class "Default")
      (node (ref "LD3") (pin "A") (pinfunction "A_A") (pintype "passive"))
      (node (ref "R51") (pin "2") (pinfunction "2_2") (pintype "passive"))
    )
    (net (code "60") (name "Net-(LD4-PadA)") (class "Default")
      (node (ref "LD4") (pin "A") (pinfunction "A_A") (pintype "passive"))
      (node (ref "R52") (pin "2") (pinfunction "2_2") (pintype "passive"))
    )
    (net (code "61") (name "Net-(LD5-PadA)") (class "Default")
      (node (ref "LD5") (pin "A") (pinfunction "A_A") (pintype "passive"))
      (node (ref "R59") (pin "1") (pinfunction "1_1") (pintype "passive"))
    )
    (net (code "62") (name "Net-(LD6-PadA)") (class "Default")
      (node (ref "LD6") (pin "A") (pinfunction "A_A") (pintype "passive"))
      (node (ref "R56") (pin "1") (pinfunction "1_1") (pintype "passive"))
    )
    (net (code "63") (name "Net-(LS1-PadN)") (class "Default")
      (node (ref "LS1") (pin "N") (pinfunction "N_N") (pintype "passive"))
      (node (ref "R36") (pin "1") (pinfunction "1_1") (pintype "passive"))
    )
    (net (code "64") (name "Net-(Q1-D)") (class "Default")
      (node (ref "D1") (pin "A") (pinfunction "A_A") (pintype "passive"))
      (node (ref "Q1") (pin "3") (pinfunction "D_3") (pintype "passive"))
      (node (ref "X2") (pin "1") (pinfunction "1_1") (pintype "passive"))
    )
    (net (code "65") (name "Net-(Q1-G)") (class "Default")
      (node (ref "Q1") (pin "1") (pinfunction "G_1") (pintype "passive"))
      (node (ref "R8") (pin "2") (pinfunction "2_2") (pintype "passive"))
    )
    (net (code "66") (name "Net-(Q2A-D1)") (class "Default")
      (node (ref "Q2") (pin "6") (pinfunction "D1_6") (pintype "passive"))
      (node (ref "R20") (pin "1") (pinfunction "1_1") (pintype "passive"))
    )
    (net (code "67") (name "Net-(Q2A-G1)") (class "Default")
      (node (ref "Q2") (pin "2") (pinfunction "G1_2") (pintype "passive"))
      (node (ref "Q2") (pin "5") (pinfunction "G2_5") (pintype "passive"))
      (node (ref "SW1") (pin "2") (pinfunction "2_2") (pintype "passive"))
      (node (ref "SW1") (pin "5") (pinfunction "5_5") (pintype "passive"))
    )
    (net (code "68") (name "Net-(Q3-D)") (class "Default")
      (node (ref "D7") (pin "A") (pinfunction "A_A") (pintype "passive"))
      (node (ref "Q3") (pin "3") (pinfunction "D_3") (pintype "passive"))
      (node (ref "X4") (pin "1") (pinfunction "1_1") (pintype "passive"))
    )
    (net (code "69") (name "Net-(Q3-G)") (class "Default")
      (node (ref "Q3") (pin "1") (pinfunction "G_1") (pintype "passive"))
      (node (ref "R21") (pin "2") (pinfunction "2_2") (pintype "passive"))
    )
    (net (code "70") (name "Net-(Q4A-D1)") (class "Default")
      (node (ref "C26") (pin "1") (pinfunction "1_1") (pintype "passive"))
      (node (ref "Q4") (pin "5") (pinfunction "G2_5") (pintype "passive"))
      (node (ref "Q4") (pin "6") (pinfunction "D1_6") (pintype "passive"))
      (node (ref "R34") (pin "2") (pinfunction "2_2") (pintype "passive"))
    )
    (net (code "71") (name "Net-(Q4A-G1)") (class "Default")
      (node (ref "Q4") (pin "2") (pinfunction "G1_2") (pintype "passive"))
      (node (ref "R39") (pin "2") (pinfunction "2_2") (pintype "passive"))
    )
    (net (code "72") (name "Net-(Q4B-D2)") (class "Default")
      (node (ref "Q4") (pin "3") (pinfunction "D2_3") (pintype "passive"))
      (node (ref "R37") (pin "1") (pinfunction "1_1") (pintype "passive"))
    )
    (net (code "73") (name "Net-(Q5-D)") (class "Default")
      (node (ref "Q5") (pin "3") (pinfunction "D_3") (pintype "passive"))
      (node (ref "R36") (pin "2") (pinfunction "2_2") (pintype "passive"))
    )
    (net (code "74") (name "Net-(Q5-G)") (class "Default")
      (node (ref "Q5") (pin "1") (pinfunction "G_1") (pintype "passive"))
      (node (ref "R38") (pin "2") (pinfunction "2_2") (pintype "passive"))
    )
    (net (code "75") (name "Net-(R1-Pad1)") (class "Default")
      (node (ref "R1") (pin "1") (pinfunction "1_1") (pintype "passive"))
      (node (ref "R4") (pin "2") (pinfunction "2_2") (pintype "passive"))
    )
    (net (code "76") (name "Net-(R3-Pad2)") (class "Default")
      (node (ref "R3") (pin "2") (pinfunction "2_2") (pintype "passive"))
      (node (ref "R5") (pin "2") (pinfunction "2_2") (pintype "passive"))
      (node (ref "R6") (pin "1") (pinfunction "1_1") (pintype "passive"))
      (node (ref "R9") (pin "2") (pinfunction "2_2") (pintype "passive"))
    )
    (net (code "77") (name "Net-(R4-Pad1)") (class "Default")
      (node (ref "R4") (pin "1") (pinfunction "1_1") (pintype "passive"))
      (node (ref "R7") (pin "2") (pinfunction "2_2") (pintype "passive"))
    )
    (net (code "78") (name "Net-(R11-Pad2)") (class "Default")
      (node (ref "R11") (pin "2") (pinfunction "2_2") (pintype "passive"))
      (node (ref "R7") (pin "1") (pinfunction "1_1") (pintype "passive"))
    )
    (net (code "79") (name "Net-(R15-Pad1)") (class "Default")
      (node (ref "R15") (pin "1") (pinfunction "1_1") (pintype "passive"))
      (node (ref "X3") (pin "1") (pinfunction "1_1") (pintype "passive"))
    )
    (net (code "80") (name "Net-(R18-Pad1)") (class "Default")
      (node (ref "R18") (pin "1") (pinfunction "1_1") (pintype "passive"))
      (node (ref "SW1") (pin "1") (pinfunction "1_1") (pintype "passive"))
      (node (ref "SW1") (pin "4") (pinfunction "4_4") (pintype "passive"))
    )
    (net (code "81") (name "Net-(R23-Pad2)") (class "Default")
      (node (ref "R23") (pin "2") (pinfunction "2_2") (pintype "passive"))
      (node (ref "R26") (pin "2") (pinfunction "2_2") (pintype "passive"))
      (node (ref "R27") (pin "1") (pinfunction "1_1") (pintype "passive"))
      (node (ref "R30") (pin "2") (pinfunction "2_2") (pintype "passive"))
    )
    (net (code "82") (name "Net-(R29-Pad1)") (class "Default")
      (node (ref "R29") (pin "1") (pinfunction "1_1") (pintype "passive"))
      (node (ref "SW1") (pin "3") (pinfunction "3_3") (pintype "passive"))
      (node (ref "SW1") (pin "6") (pinfunction "6_6") (pintype "passive"))
    )
    (net (code "83") (name "Net-(R33-Pad1)") (class "Default")
      (node (ref "R33") (pin "1") (pinfunction "1_1") (pintype "passive"))
      (node (ref "X5") (pin "1") (pinfunction "1_1") (pintype "passive"))
    )
    (net (code "84") (name "Net-(R46-Pad1)") (class "Default")
      (node (ref "R46") (pin "1") (pinfunction "1_1") (pintype "passive"))
      (node (ref "R50") (pin "1") (pinfunction "1_1") (pintype "passive"))
      (node (ref "X7") (pin "4") (pinfunction "4_4") (pintype "passive"))
    )
    (net (code "85") (name "Net-(R47-Pad1)") (class "Default")
      (node (ref "R47") (pin "1") (pinfunction "1_1") (pintype "passive"))
      (node (ref "R54") (pin "2") (pinfunction "2_2") (pintype "passive"))
      (node (ref "X7") (pin "2") (pinfunction "2_2") (pintype "passive"))
    )
    (net (code "86") (name "Net-(R53-Pad1)") (class "Default")
      (node (ref "R53") (pin "1") (pinfunction "1_1") (pintype "passive"))
      (node (ref "X7") (pin "5") (pinfunction "5_5") (pintype "passive"))
    )
    (net (code "87") (name "Net-(U1-VOUT)") (class "Default")
      (node (ref "C4") (pin "1") (pinfunction "1_1") (pintype "passive"))
      (node (ref "FB1") (pin "2") (pinfunction "2_2") (pintype "passive"))
      (node (ref "U1") (pin "3") (pinfunction "VOUT_3") (pintype "power_in"))
    )
    (net (code "88") (name "Net-(U2-VOUT)") (class "Default")
      (node (ref "C10") (pin "1") (pinfunction "1_1") (pintype "passive"))
      (node (ref "FB2") (pin "2") (pinfunction "2_2") (pintype "passive"))
      (node (ref "U2") (pin "3") (pinfunction "VOUT_3") (pintype "power_in"))
    )
    (net (code "89") (name "Net-(U3-EN)") (class "Default")
      (node (ref "BU1") (pin "3") (pinfunction "3_3") (pintype "passive"))
      (node (ref "BU1") (pin "4") (pinfunction "4_4") (pintype "passive"))
      (node (ref "R24") (pin "2") (pinfunction "2_2") (pintype "passive"))
      (node (ref "R25") (pin "1") (pinfunction "1_1") (pintype "passive"))
      (node (ref "U3") (pin "1") (pinfunction "EN_1") (pintype "input"))
    )
    (net (code "90") (name "Net-(U3-VIN)") (class "Default")
      (node (ref "C16") (pin "1") (pinfunction "1_1") (pintype "passive"))
      (node (ref "C17") (pin "1") (pinfunction "1_1") (pintype "passive"))
      (node (ref "FB3") (pin "1") (pinfunction "1_1") (pintype "passive"))
      (node (ref "R24") (pin "1") (pinfunction "1_1") (pintype "passive"))
      (node (ref "U3") (pin "6") (pinfunction "VIN_6") (pintype "power_in"))
    )
    (net (code "91") (name "Net-(U4-BOOT0)") (class "Default")
      (node (ref "R40") (pin "1") (pinfunction "1_1") (pintype "passive"))
      (node (ref "R44") (pin "2") (pinfunction "2_2") (pintype "passive"))
      (node (ref "U4") (pin "60") (pinfunction "BOOT0_60") (pintype "passive"))
    )
    (net (code "92") (name "Net-(U4-PC6)") (class "Default")
      (node (ref "TP1") (pin "1") (pinfunction "1_1") (pintype "passive"))
      (node (ref "U4") (pin "37") (pinfunction "PC6_37") (pintype "bidirectional"))
    )
    (net (code "93") (name "Net-(U4-PC7)") (class "Default")
      (node (ref "TP2") (pin "1") (pinfunction "1_1") (pintype "passive"))
      (node (ref "U4") (pin "38") (pinfunction "PC7_38") (pintype "bidirectional"))
    )
    (net (code "94") (name "Net-(U4-PC8)") (class "Default")
      (node (ref "TP3") (pin "1") (pinfunction "1_1") (pintype "passive"))
      (node (ref "U4") (pin "39") (pinfunction "PC8_39") (pintype "bidirectional"))
    )
    (net (code "95") (name "Net-(U4-PF0{slash}OSC_IN)") (class "Default")
      (node (ref "C41") (pin "1") (pinfunction "1_1") (pintype "passive"))
      (node (ref "U4") (pin "5") (pinfunction "PF0/OSC_IN_5") (pintype "bidirectional"))
      (node (ref "Y1") (pin "1") (pinfunction "1_1") (pintype "passive"))
    )
    (net (code "96") (name "Net-(U4-PF1{slash}OSC_OUT)") (class "Default")
      (node (ref "R64") (pin "2") (pinfunction "2_2") (pintype "passive"))
      (node (ref "U4") (pin "6") (pinfunction "PF1/OSC_OUT_6") (pintype "bidirectional"))
    )
    (net (code "97") (name "Net-(U5-IN+)") (class "Default")
      (node (ref "R42") (pin "1") (pinfunction "1_1") (pintype "passive"))
      (node (ref "R45") (pin "1") (pinfunction "1_1") (pintype "passive"))
      (node (ref "U5") (pin "3") (pinfunction "IN+_3") (pintype "input"))
    )
    (net (code "98") (name "Net-(U5-IN-)") (class "Default")
      (node (ref "R48") (pin "2") (pinfunction "2_2") (pintype "passive"))
      (node (ref "R49") (pin "2") (pinfunction "2_2") (pintype "passive"))
      (node (ref "U5") (pin "4") (pinfunction "IN-_4") (pintype "input"))
    )
    (net (code "99") (name "Net-(U5-OUT)") (class "Default")
      (node (ref "R43") (pin "2") (pinfunction "2_2") (pintype "passive"))
      (node (ref "R48") (pin "1") (pinfunction "1_1") (pintype "passive"))
      (node (ref "U5") (pin "1") (pinfunction "OUT_1") (pintype "output"))
    )
    (net (code "100") (name "Net-(U6-RXD)") (class "Default")
      (node (ref "R66") (pin "1") (pinfunction "1_1") (pintype "passive"))
      (node (ref "U6") (pin "25") (pinfunction "RXD_25") (pintype "input"))
    )
    (net (code "101") (name "Net-(U6-TXD)") (class "Default")
      (node (ref "LD5") (pin "C") (pinfunction "C_C") (pintype "passive"))
      (node (ref "R58") (pin "1") (pinfunction "1_1") (pintype "passive"))
      (node (ref "R65") (pin "1") (pinfunction "1_1") (pintype "passive"))
      (node (ref "U6") (pin "26") (pinfunction "TXD_26") (pintype "output"))
    )
    (net (code "102") (name "Net-(U6-VBUS)") (class "Default")
      (node (ref "R60") (pin "2") (pinfunction "2_2") (pintype "passive"))
      (node (ref "R62") (pin "1") (pinfunction "1_1") (pintype "passive"))
      (node (ref "U6") (pin "8") (pinfunction "VBUS_8") (pintype "power_in"))
    )
    (net (code "103") (name "Net-(U6-VDD)") (class "Default")
      (node (ref "C39") (pin "2") (pinfunction "2_2") (pintype "passive"))
      (node (ref "R68") (pin "2") (pinfunction "2_2") (pintype "passive"))
      (node (ref "U6") (pin "6") (pinfunction "VDD_6") (pintype "power_in"))
    )
    (net (code "104") (name "Net-(U6-~{RST})") (class "Default")
      (node (ref "R61") (pin "2") (pinfunction "2_2") (pintype "passive"))
      (node (ref "U6") (pin "9") (pinfunction "~{RST}_9") (pintype "bidirectional"))
    )
    (net (code "105") (name "Net-(U7-SCL2)") (class "Default")
      (node (ref "R70") (pin "1") (pinfunction "1_1") (pintype "passive"))
      (node (ref "U7") (pin "6") (pinfunction "SCL2_6") (pintype "bidirectional"))
      (node (ref "X9") (pin "1") (pinfunction "1_1") (pintype "passive"))
    )
    (net (code "106") (name "Net-(U7-SDA2)") (class "Default")
      (node (ref "R69") (pin "1") (pinfunction "1_1") (pintype "passive"))
      (node (ref "U7") (pin "7") (pinfunction "SDA2_7") (pintype "bidirectional"))
      (node (ref "X9") (pin "2") (pinfunction "2_2") (pintype "passive"))
    )
    (net (code "107") (name "PWM_HL") (class "Default")
      (node (ref "R32") (pin "2") (pinfunction "2_2") (pintype "passive"))
    )
    (net (code "108") (name "PWM_HR") (class "Default")
      (node (ref "R6") (pin "2") (pinfunction "2_2") (pintype "passive"))
    )
    (net (code "109") (name "PWM_LL") (class "Default")
      (node (ref "R12") (pin "2") (pinfunction "2_2") (pintype "passive"))
    )
    (net (code "110") (name "PWM_LR") (class "Default")
      (node (ref "R27") (pin "2") (pinfunction "2_2") (pintype "passive"))
    )
    (net (code "111") (name "Shield") (class "Default")
      (node (ref "C44") (pin "1") (pinfunction "1_1") (pintype "passive"))
      (node (ref "H1") (pin "1") (pinfunction "1_1") (pintype "passive"))
      (node (ref "R84") (pin "1") (pinfunction "1_1") (pintype "passive"))
    )
    (net (code "112") (name "unconnected-(BT1-Pad1)") (class "Default")
      (node (ref "BT1") (pin "1") (pinfunction "1_1") (pintype "passive"))
    )
    (net (code "113") (name "unconnected-(BT1-Pad2)") (class "Default")
      (node (ref "BT1") (pin "2") (pinfunction "2_2") (pintype "passive"))
    )
    (net (code "114") (name "unconnected-(H2-Pad1)") (class "Default")
      (node (ref "H2") (pin "1") (pinfunction "1_1") (pintype "passive+no_connect"))
    )
    (net (code "115") (name "unconnected-(H3-Pad1)") (class "Default")
      (node (ref "H3") (pin "1") (pinfunction "1_1") (pintype "passive+no_connect"))
    )
    (net (code "116") (name "unconnected-(H4-Pad1)") (class "Default")
      (node (ref "H4") (pin "1") (pinfunction "1_1") (pintype "passive+no_connect"))
    )
    (net (code "117") (name "unconnected-(U3-NC-Pad5)") (class "Default")
      (node (ref "U3") (pin "5") (pinfunction "NC_5") (pintype "passive"))
    )
    (net (code "118") (name "unconnected-(U3-PG-Pad3)") (class "Default")
      (node (ref "U3") (pin "3") (pinfunction "PG_3") (pintype "passive+no_connect"))
    )
    (net (code "119") (name "unconnected-(U4-PA6-Pad22)") (class "Default")
      (node (ref "U4") (pin "22") (pinfunction "PA6_22") (pintype "bidirectional"))
    )
    (net (code "120") (name "unconnected-(U4-PA7-Pad23)") (class "Default")
      (node (ref "U4") (pin "23") (pinfunction "PA7_23") (pintype "bidirectional"))
    )
    (net (code "121") (name "unconnected-(U4-PA15-Pad50)") (class "Default")
      (node (ref "U4") (pin "50") (pinfunction "PA15_50") (pintype "bidirectional"))
    )
    (net (code "122") (name "unconnected-(U4-PB2-Pad28)") (class "Default")
      (node (ref "U4") (pin "28") (pinfunction "PB2_28") (pintype "bidirectional"))
    )
    (net (code "123") (name "unconnected-(U4-PB3-Pad55)") (class "Default")
      (node (ref "U4") (pin "55") (pinfunction "PB3_55") (pintype "bidirectional"))
    )
    (net (code "124") (name "unconnected-(U4-PB5-Pad57)") (class "Default")
      (node (ref "U4") (pin "57") (pinfunction "PB5_57") (pintype "bidirectional"))
    )
    (net (code "125") (name "unconnected-(U4-PB10-Pad29)") (class "Default")
      (node (ref "U4") (pin "29") (pinfunction "PB10_29") (pintype "bidirectional"))
    )
    (net (code "126") (name "unconnected-(U4-PB11-Pad30)") (class "Default")
      (node (ref "U4") (pin "30") (pinfunction "PB11_30") (pintype "bidirectional"))
    )
    (net (code "127") (name "unconnected-(U4-PB14-Pad35)") (class "Default")
      (node (ref "U4") (pin "35") (pinfunction "PB14_35") (pintype "bidirectional"))
    )
    (net (code "128") (name "unconnected-(U4-PB15-Pad36)") (class "Default")
      (node (ref "U4") (pin "36") (pinfunction "PB15_36") (pintype "bidirectional"))
    )
    (net (code "129") (name "unconnected-(U4-PC0-Pad8)") (class "Default")
      (node (ref "U4") (pin "8") (pinfunction "PC0_8") (pintype "bidirectional"))
    )
    (net (code "130") (name "unconnected-(U4-PC1-Pad9)") (class "Default")
      (node (ref "U4") (pin "9") (pinfunction "PC1_9") (pintype "bidirectional"))
    )
    (net (code "131") (name "unconnected-(U4-PC2-Pad10)") (class "Default")
      (node (ref "U4") (pin "10") (pinfunction "PC2_10") (pintype "bidirectional"))
    )
    (net (code "132") (name "unconnected-(U4-PC3-Pad11)") (class "Default")
      (node (ref "U4") (pin "11") (pinfunction "PC3_11") (pintype "bidirectional"))
    )
    (net (code "133") (name "unconnected-(U4-PC9-Pad40)") (class "Default")
      (node (ref "U4") (pin "40") (pinfunction "PC9_40") (pintype "bidirectional"))
    )
    (net (code "134") (name "unconnected-(U4-PC10-Pad51)") (class "Default")
      (node (ref "U4") (pin "51") (pinfunction "PC10_51") (pintype "bidirectional"))
    )
    (net (code "135") (name "unconnected-(U4-PC11-Pad52)") (class "Default")
      (node (ref "U4") (pin "52") (pinfunction "PC11_52") (pintype "bidirectional"))
    )
    (net (code "136") (name "unconnected-(U4-PD2-Pad54)") (class "Default")
      (node (ref "U4") (pin "54") (pinfunction "PD2_54") (pintype "bidirectional+no_connect"))
    )
    (net (code "137") (name "unconnected-(U6-SUSP-Pad12)") (class "Default")
      (node (ref "U6") (pin "12") (pinfunction "SUSP_12") (pintype "output+no_connect"))
    )
    (net (code "138") (name "unconnected-(U6-VPP-Pad18)") (class "Default")
      (node (ref "U6") (pin "18") (pinfunction "VPP_18") (pintype "bidirectional+no_connect"))
    )
    (net (code "139") (name "unconnected-(U6-~{CTS}-Pad23)") (class "Default")
      (node (ref "U6") (pin "23") (pinfunction "~{CTS}_23") (pintype "input+no_connect"))
    )
    (net (code "140") (name "unconnected-(U6-~{DCD}-Pad1)") (class "Default")
      (node (ref "U6") (pin "1") (pinfunction "~{DCD}_1") (pintype "input+no_connect"))
    )
    (net (code "141") (name "unconnected-(U6-~{DSR}-Pad27)") (class "Default")
      (node (ref "U6") (pin "27") (pinfunction "~{DSR}_27") (pintype "input+no_connect"))
    )
    (net (code "142") (name "unconnected-(U6-~{DTR}-Pad28)") (class "Default")
      (node (ref "U6") (pin "28") (pinfunction "~{DTR}_28") (pintype "output+no_connect"))
    )
    (net (code "143") (name "unconnected-(U6-~{RI}-Pad2)") (class "Default")
      (node (ref "U6") (pin "2") (pinfunction "~{RI}_2") (pintype "input+no_connect"))
    )
    (net (code "144") (name "unconnected-(U6-~{RTS}-Pad24)") (class "Default")
      (node (ref "U6") (pin "24") (pinfunction "~{RTS}_24") (pintype "output+no_connect"))
    )
    (net (code "145") (name "unconnected-(U6-~{SUSP}-Pad11)") (class "Default")
      (node (ref "U6") (pin "11") (pinfunction "~{SUSP}_11") (pintype "output+no_connect"))
    )
    (net (code "146") (name "unconnected-(X8-CC1-PadA5)") (class "Default")
      (node (ref "X8") (pin "A5") (pinfunction "CC1_A5") (pintype "bidirectional+no_connect"))
    )
    (net (code "147") (name "unconnected-(X8-RX1+-PadB11)") (class "Default")
      (node (ref "X8") (pin "B11") (pinfunction "RX1+_B11") (pintype "bidirectional+no_connect"))
    )
    (net (code "148") (name "unconnected-(X8-RX1--PadB10)") (class "Default")
      (node (ref "X8") (pin "B10") (pinfunction "RX1-_B10") (pintype "bidirectional+no_connect"))
    )
    (net (code "149") (name "unconnected-(X8-RX2+-PadA11)") (class "Default")
      (node (ref "X8") (pin "A11") (pinfunction "RX2+_A11") (pintype "bidirectional+no_connect"))
    )
    (net (code "150") (name "unconnected-(X8-RX2--PadA10)") (class "Default")
      (node (ref "X8") (pin "A10") (pinfunction "RX2-_A10") (pintype "bidirectional+no_connect"))
    )
    (net (code "151") (name "unconnected-(X8-SBU1-PadA8)") (class "Default")
      (node (ref "X8") (pin "A8") (pinfunction "SBU1_A8") (pintype "bidirectional+no_connect"))
    )
    (net (code "152") (name "unconnected-(X8-SBU2-PadB8)") (class "Default")
      (node (ref "X8") (pin "B8") (pinfunction "SBU2_B8") (pintype "bidirectional+no_connect"))
    )
    (net (code "153") (name "unconnected-(X8-TX1+-PadA2)") (class "Default")
      (node (ref "X8") (pin "A2") (pinfunction "TX1+_A2") (pintype "bidirectional+no_connect"))
    )
    (net (code "154") (name "unconnected-(X8-TX1--PadA3)") (class "Default")
      (node (ref "X8") (pin "A3") (pinfunction "TX1-_A3") (pintype "bidirectional+no_connect"))
    )
    (net (code "155") (name "unconnected-(X8-TX2+-PadB2)") (class "Default")
      (node (ref "X8") (pin "B2") (pinfunction "TX2+_B2") (pintype "bidirectional+no_connect"))
    )
    (net (code "156") (name "unconnected-(X8-TX2--PadB3)") (class "Default")
      (node (ref "X8") (pin "B3") (pinfunction "TX2-_B3") (pintype "bidirectional+no_connect"))
    )
    (net (code "157") (name "unconnected-(X8-VCON-PadB5)") (class "Default")
      (node (ref "X8") (pin "B5") (pinfunction "VCON_B5") (pintype "bidirectional+no_connect"))
    )
  )
)
